# design.net
KiCad netlist of a schematic drawn in Altium Designer
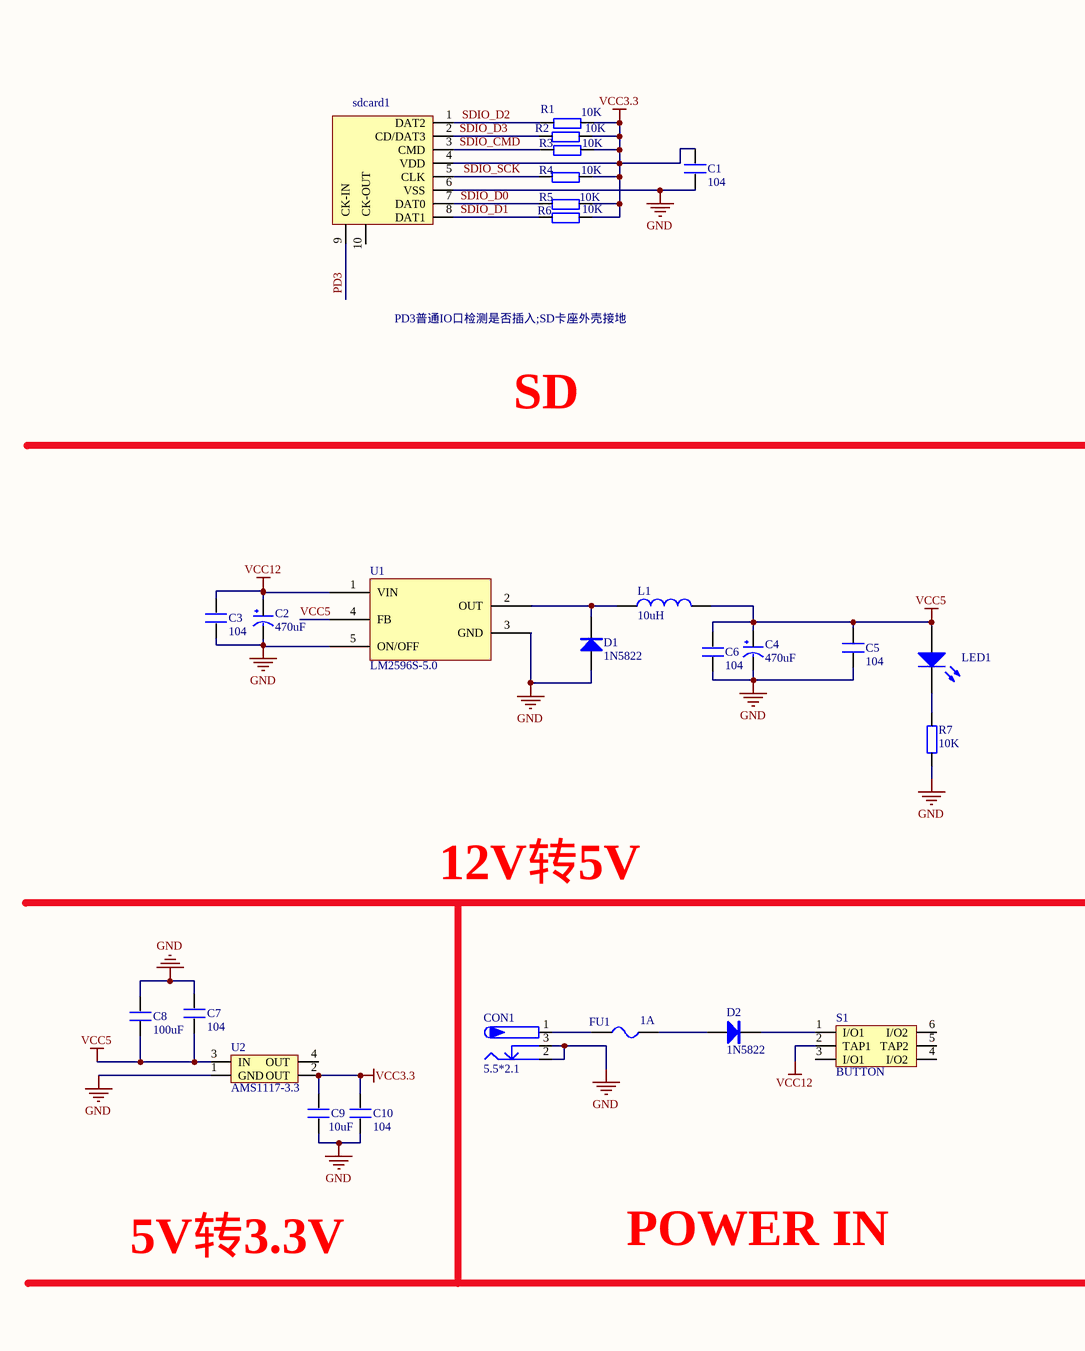
[diagram p0: 门禁原理图.SchDoc, top left]
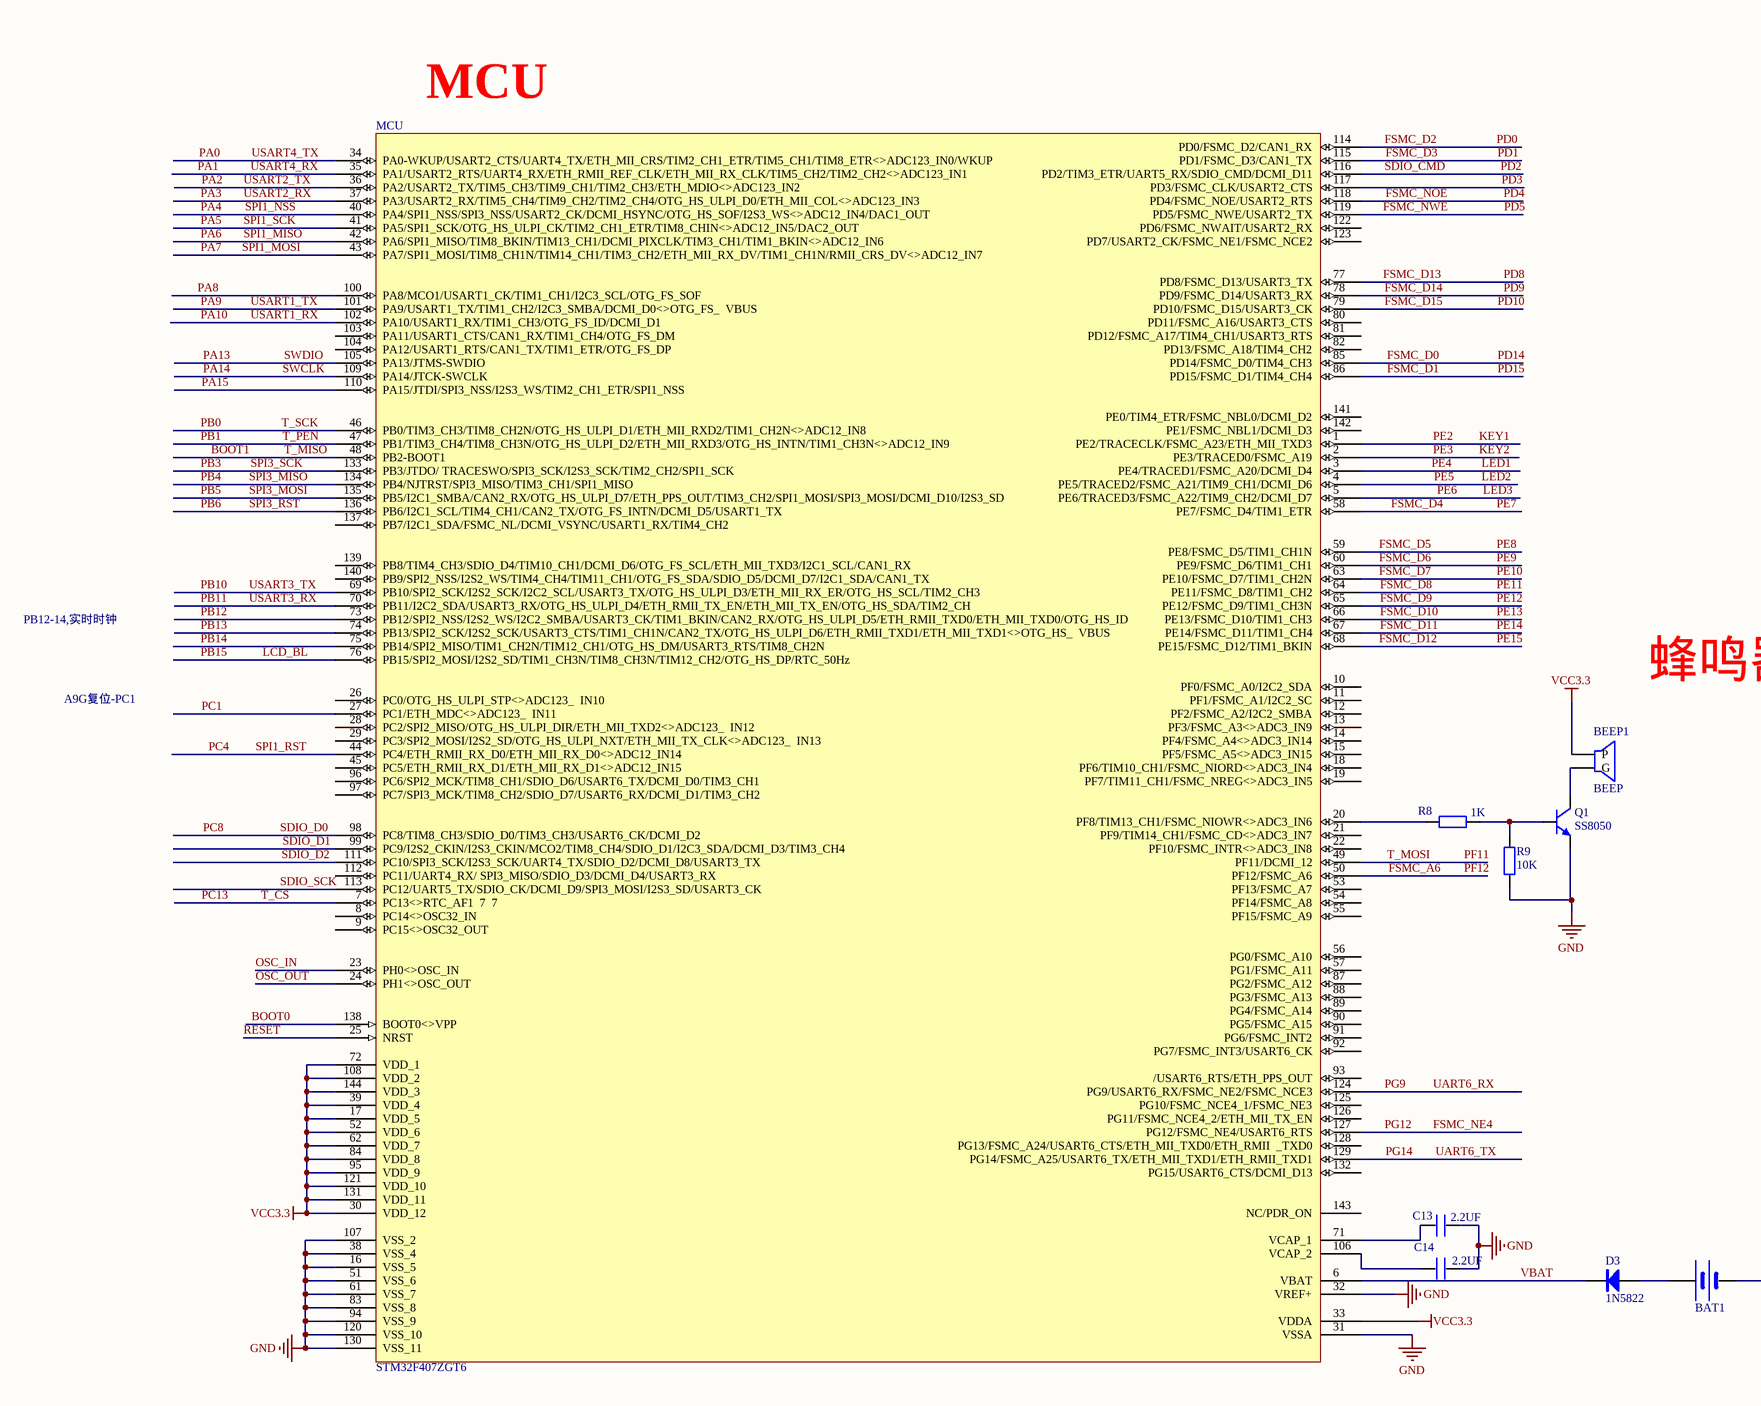
[diagram p1: 门禁原理图.SchDoc, top middle]
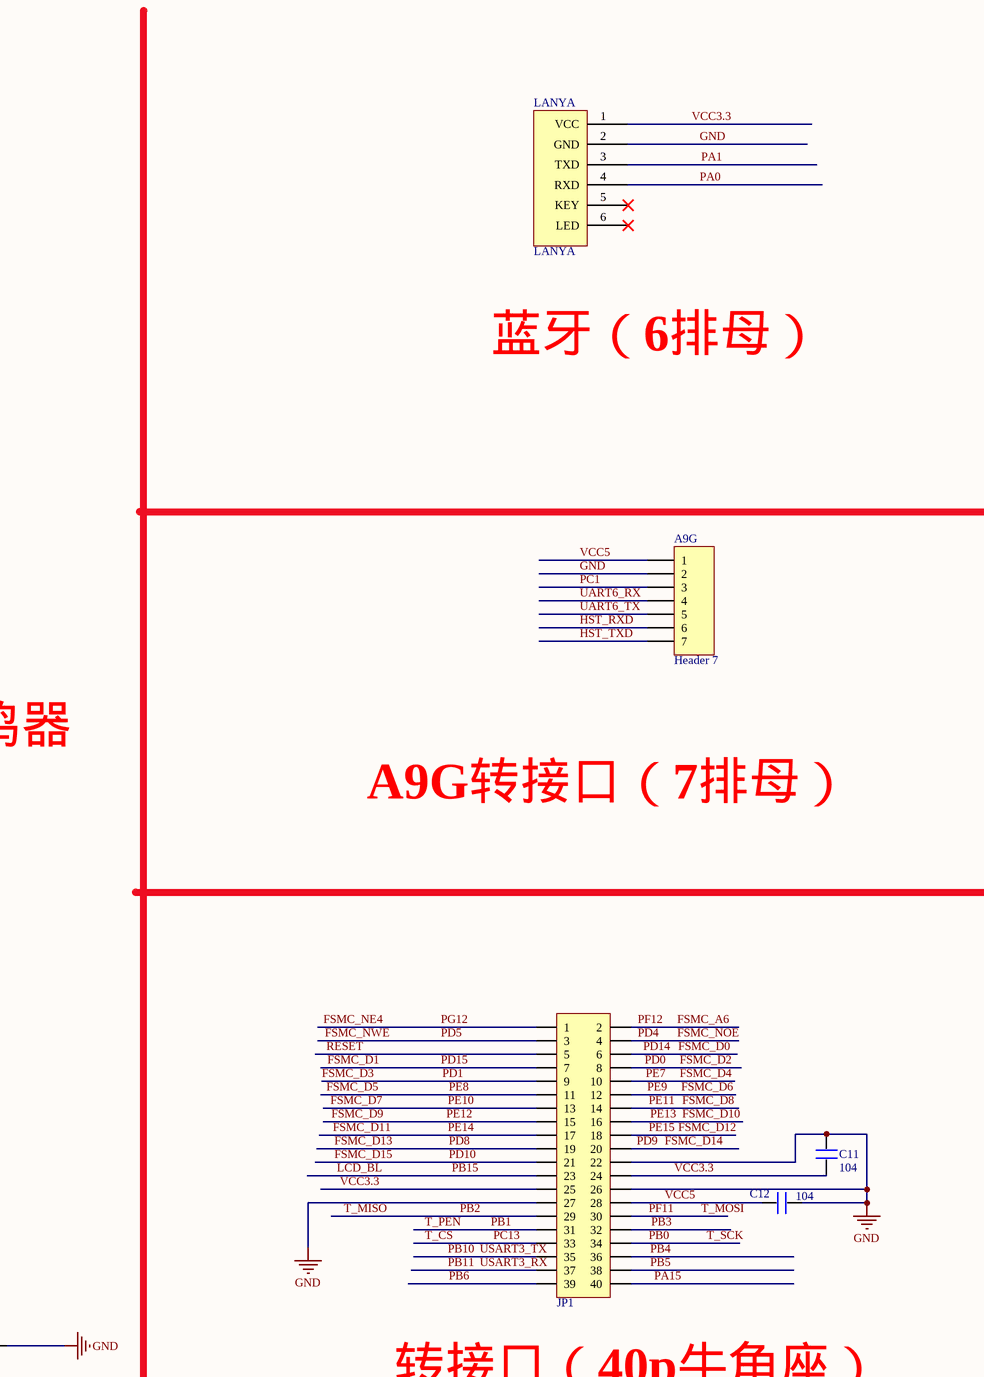
[diagram p2: 门禁原理图.SchDoc, top right]
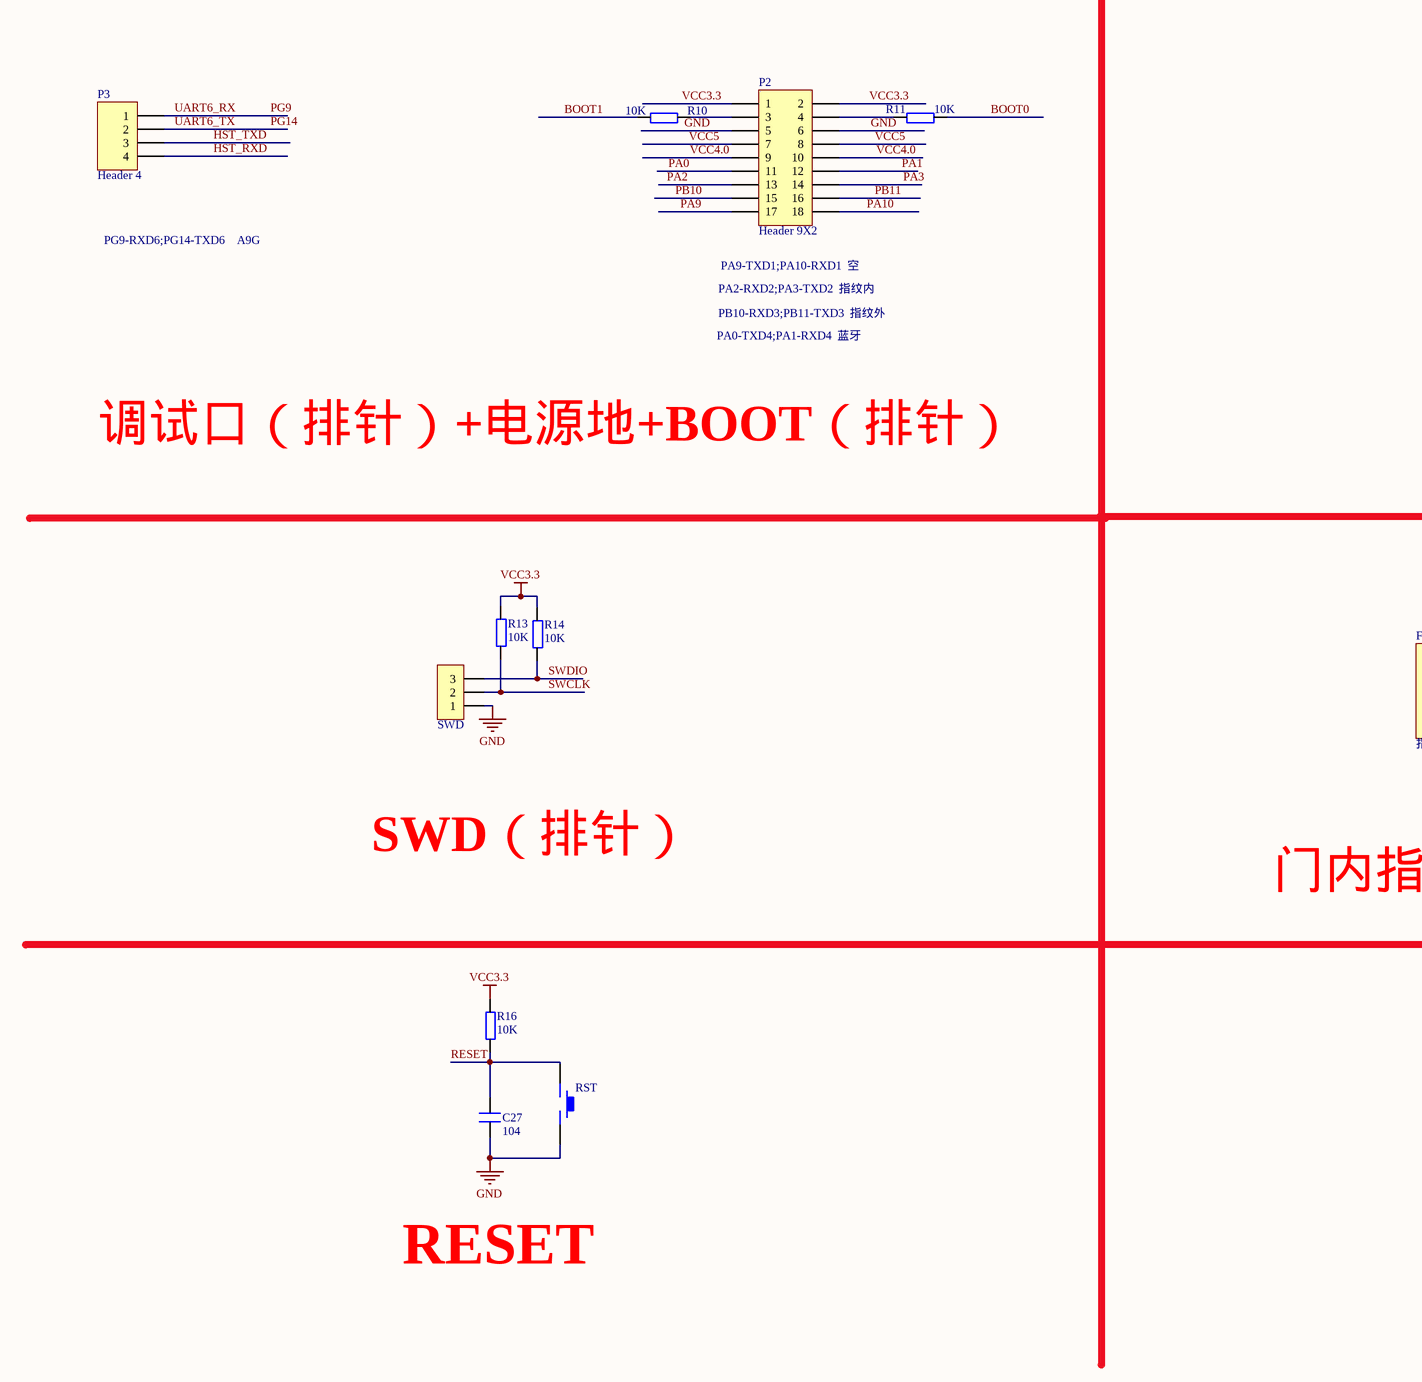
[diagram p3: 门禁原理图.SchDoc, bottom left]
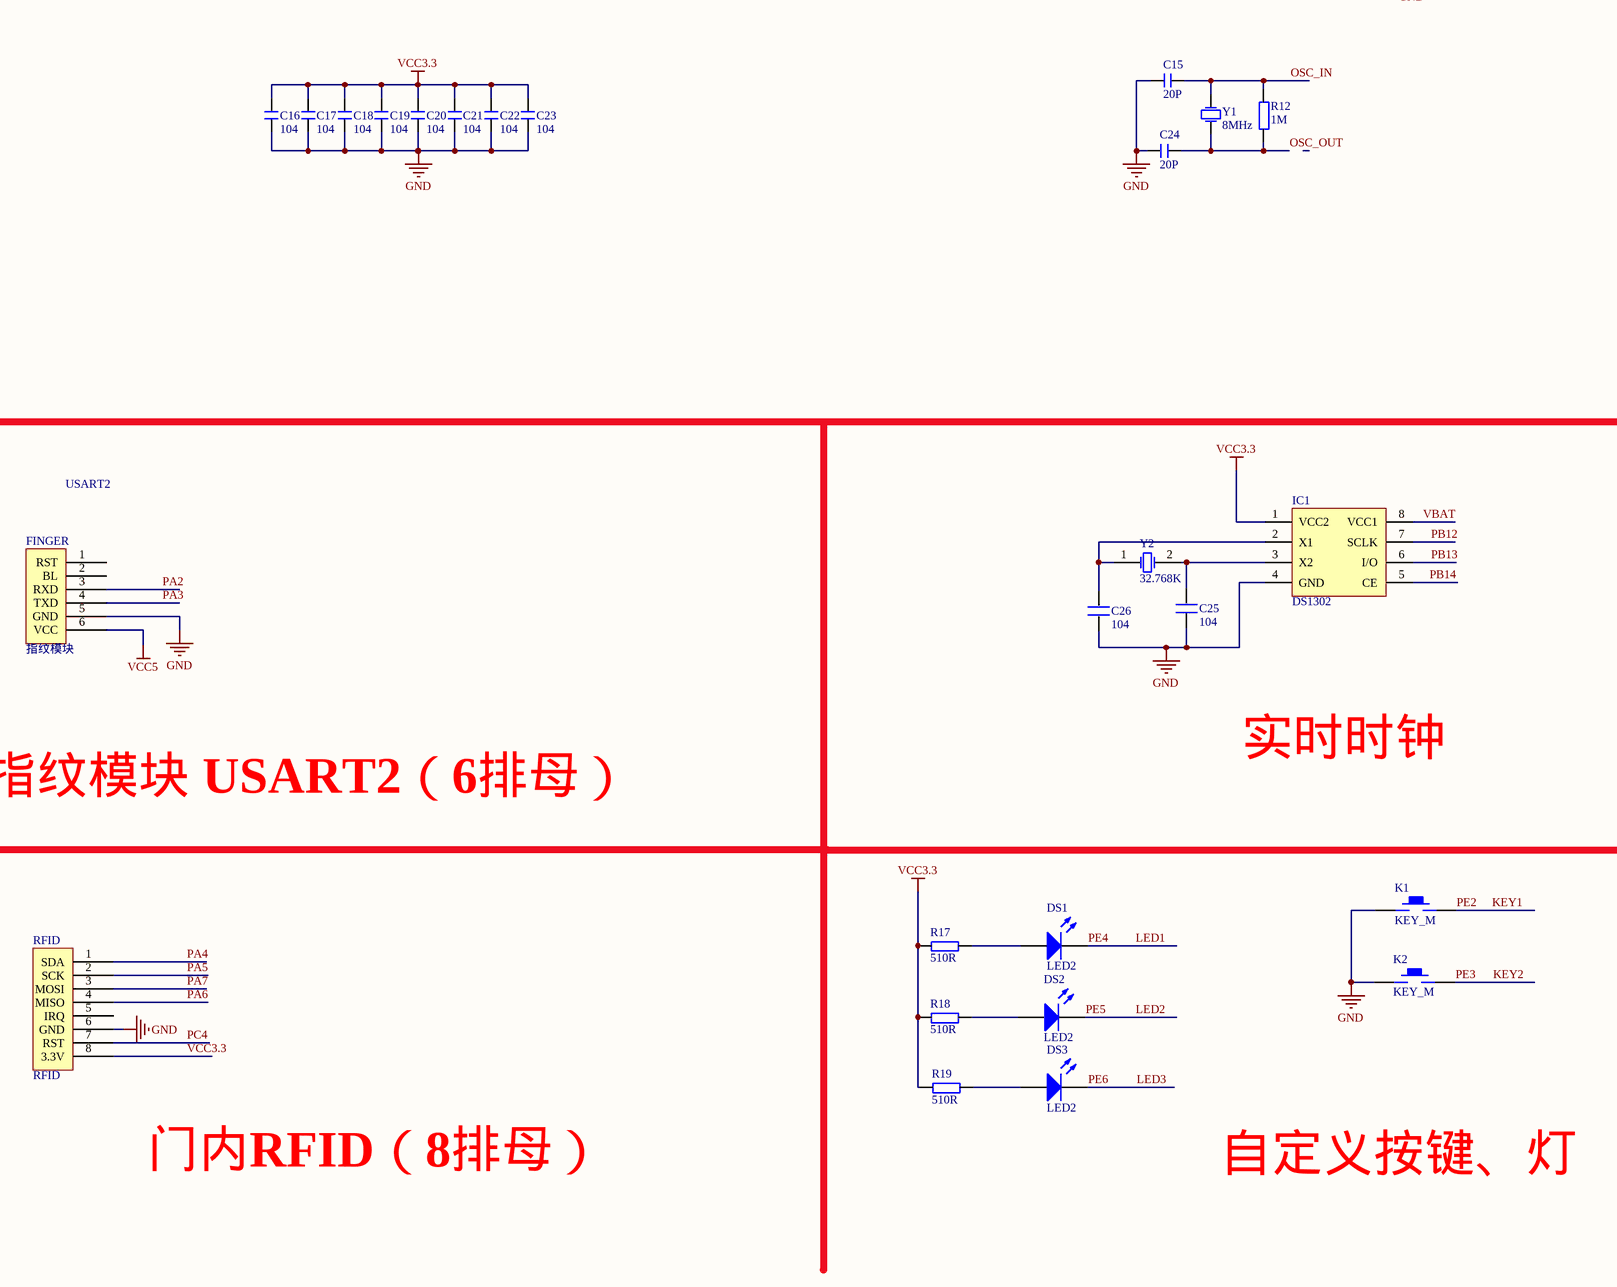
[diagram p4: 门禁原理图.SchDoc, bottom middle]
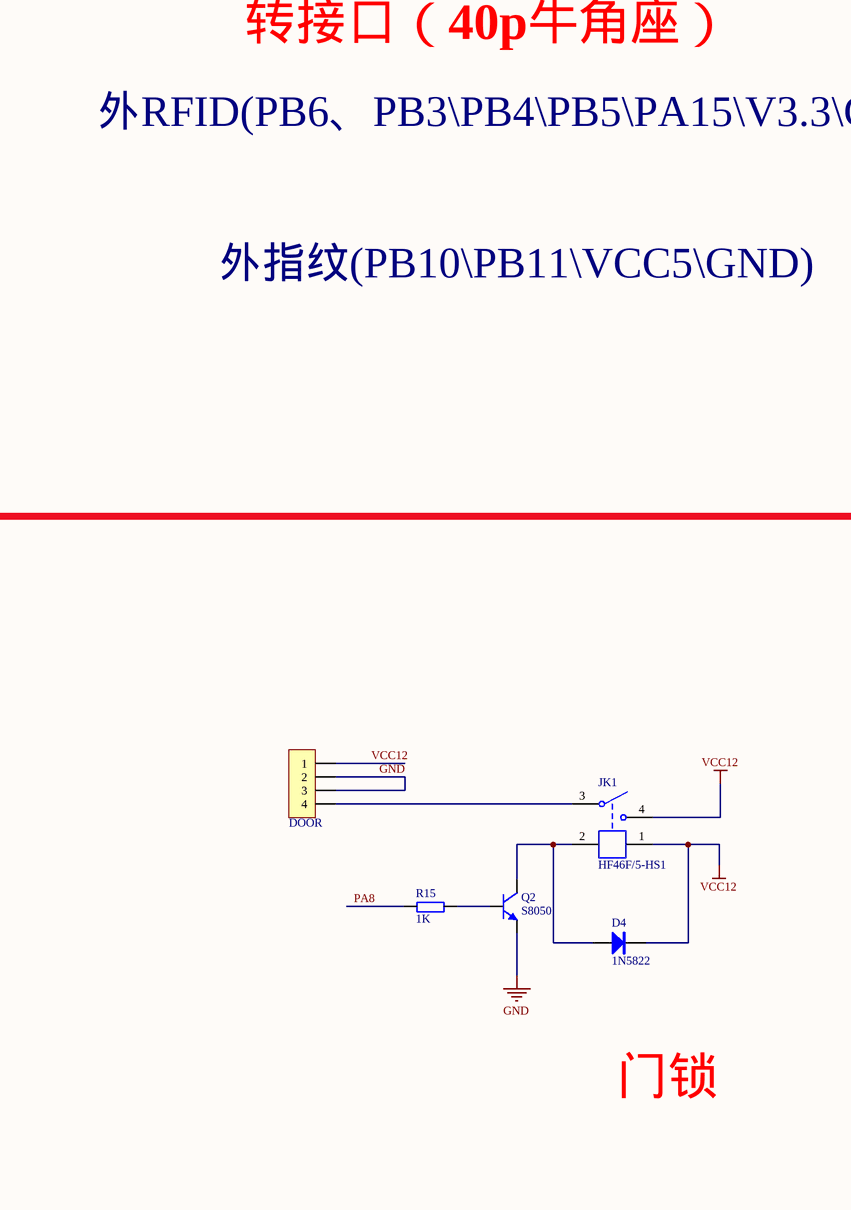
[diagram p5: 门禁原理图.SchDoc, bottom right]

(export (version "E")
  (design (tool "Eeschema 10.0.6"))
  (components
    (comp (ref "A9G")
      (value "Header 7")
      (footprint "A9G")
      (description "Header, 7-Pin")
      (fields (field (name "PUBLISHER") "Altium Limited"))
      (libsource (lib "Miscellaneous Connectors") (part "Header 7"))
    )
    (comp (ref "BAT1") (value "BATT") (footprint "BATMAX") (libsource (lib "门禁系统") (part "BAT")))
    (comp (ref "BEEP1") (value "BEEP") (footprint "BUZZ") (libsource (lib "门禁系统") (part "BEEP")))
    (comp (ref "C1") (value "104") (footprint "0805") (libsource (lib "Explorer STM32F407封装库") (part "C")))
    (comp (ref "C2") (value "470uF") (footprint "CM F(10*10.2)") (libsource (lib "门禁系统") (part "CAP")))
    (comp (ref "C3") (value "104") (footprint "0805") (libsource (lib "门禁系统") (part "C")))
    (comp (ref "C4") (value "470uF") (footprint "CM F(10*10.2)") (libsource (lib "门禁系统") (part "CAP")))
    (comp (ref "C5") (value "104") (footprint "0805") (libsource (lib "门禁系统") (part "C")))
    (comp (ref "C6") (value "104") (footprint "0805") (libsource (lib "门禁系统") (part "C")))
    (comp (ref "C7") (value "104") (footprint "0603P") (libsource (lib "Explorer STM32F407封装库") (part "C")))
    (comp (ref "C8")
      (value "100uF")
      (footprint "CM D(6.3*7.7)")
      (libsource (lib "Explorer STM32F407封装库") (part "C"))
    )
    (comp (ref "C9") (value "10uF") (footprint "0603P") (libsource (lib "Explorer STM32F407封装库") (part "C")))
    (comp (ref "C10") (value "104") (footprint "0603P") (libsource (lib "Explorer STM32F407封装库") (part "C")))
    (comp (ref "C11") (value "104") (footprint "0805") (libsource (lib "Explorer STM32F407封装库") (part "C")))
    (comp (ref "C12") (value "104") (footprint "0805") (libsource (lib "Explorer STM32F407封装库") (part "C")))
    (comp (ref "C13")
      (value "2.2UF")
      (footprint "0805")
      (libsource (lib "Explorer STM32F407封装库_SCH") (part "C_1"))
    )
    (comp (ref "C14")
      (value "2.2UF")
      (footprint "0805")
      (libsource (lib "Explorer STM32F407封装库_SCH") (part "C_1"))
    )
    (comp (ref "C15")
      (value "20P")
      (footprint "0805")
      (description "无极性贴片电容")
      (fields (field (name "版权归属") "源创客"))
      (libsource (lib "3.1   - 电阻-电容-电感") (part "C"))
    )
    (comp (ref "C16")
      (value "104")
      (footprint "0805")
      (description "无极性贴片电容")
      (fields (field (name "版权归属") "源创客"))
      (libsource (lib "3.1   - 电阻-电容-电感") (part "C"))
    )
    (comp (ref "C17")
      (value "104")
      (footprint "0805")
      (description "无极性贴片电容")
      (fields (field (name "版权归属") "源创客"))
      (libsource (lib "3.1   - 电阻-电容-电感") (part "C"))
    )
    (comp (ref "C18")
      (value "104")
      (footprint "0805")
      (description "无极性贴片电容")
      (fields (field (name "版权归属") "源创客"))
      (libsource (lib "3.1   - 电阻-电容-电感") (part "C"))
    )
    (comp (ref "C19")
      (value "104")
      (footprint "0805")
      (description "无极性贴片电容")
      (fields (field (name "版权归属") "源创客"))
      (libsource (lib "3.1   - 电阻-电容-电感") (part "C"))
    )
    (comp (ref "C20")
      (value "104")
      (footprint "0805")
      (description "无极性贴片电容")
      (fields (field (name "版权归属") "源创客"))
      (libsource (lib "3.1   - 电阻-电容-电感") (part "C"))
    )
    (comp (ref "C21")
      (value "104")
      (footprint "0805")
      (description "无极性贴片电容")
      (fields (field (name "版权归属") "源创客"))
      (libsource (lib "3.1   - 电阻-电容-电感") (part "C"))
    )
    (comp (ref "C22")
      (value "104")
      (footprint "0805")
      (description "无极性贴片电容")
      (fields (field (name "版权归属") "源创客"))
      (libsource (lib "3.1   - 电阻-电容-电感") (part "C"))
    )
    (comp (ref "C23")
      (value "104")
      (footprint "0805")
      (description "无极性贴片电容")
      (fields (field (name "版权归属") "源创客"))
      (libsource (lib "3.1   - 电阻-电容-电感") (part "C"))
    )
    (comp (ref "C24")
      (value "20P")
      (footprint "0805")
      (description "无极性贴片电容")
      (fields (field (name "版权归属") "源创客"))
      (libsource (lib "3.1   - 电阻-电容-电感") (part "C"))
    )
    (comp (ref "C25") (value "104") (footprint "0805") (libsource (lib "门禁系统") (part "C")))
    (comp (ref "C26") (value "104") (footprint "0805") (libsource (lib "门禁系统") (part "C")))
    (comp (ref "C27")
      (value "104")
      (footprint "0603P")
      (libsource (lib "Explorer STM32F407封装库_SCH") (part "C"))
    )
    (comp (ref "CON1")
      (value "5.5*2.1")
      (footprint "DC-005")
      (description "低压电源接口")
      (fields (field (name "版权归属") "源创客"))
      (libsource (lib "4.1   - 接口类") (part "P-DC"))
    )
    (comp (ref "D1")
      (value "1N5822")
      (footprint "DIODE_3*5.3")
      (description "高速开关二极管")
      (fields (field (name "版权归属") "源创客"))
      (libsource (lib "8.1   - 二极管-整流桥") (part "1N4148"))
    )
    (comp (ref "D2")
      (value "1N5822")
      (footprint "DIODE_3*5.3")
      (description "高速开关二极管")
      (fields (field (name "版权归属") "源创客"))
      (libsource (lib "8.1   - 二极管-整流桥") (part "1N4148"))
    )
    (comp (ref "D3")
      (value "1N5822")
      (footprint "DIODE_3*5.3")
      (description "高速开关二极管")
      (fields (field (name "版权归属") "源创客"))
      (libsource (lib "8.1   - 二极管-整流桥") (part "1N4148"))
    )
    (comp (ref "D4")
      (value "1N5822")
      (footprint "DIODE_3*5.3")
      (description "高速开关二极管")
      (fields (field (name "版权归属") "源创客"))
      (libsource (lib "8.1   - 二极管-整流桥") (part "1N4148"))
    )
    (comp (ref "DOOR")
      (value "HDR-1X4")
      (footprint "XH2.54-WI-4P")
      (description "4P接插件")
      (fields (field (name "版权归属") "源创客"))
      (libsource (lib "4.5   - 接插件-脚距2.54") (part "Header 4"))
    )
    (comp (ref "DS1")
      (value "LED2")
      (footprint "SMDLED")
      (description "Typical RED, GREEN, YELLOW, AMBER GaAs LED")
      (fields (field (name "PUBLISHER") "*"))
      (libsource (lib "Explorer STM32F407封装库_SCH") (part "LED2"))
    )
    (comp (ref "DS2")
      (value "LED2")
      (footprint "SMDLED")
      (description "Typical RED, GREEN, YELLOW, AMBER GaAs LED")
      (fields (field (name "PUBLISHER") "*"))
      (libsource (lib "Explorer STM32F407封装库_SCH") (part "LED2"))
    )
    (comp (ref "DS3")
      (value "LED2")
      (footprint "SMDLED")
      (description "Typical RED, GREEN, YELLOW, AMBER GaAs LED")
      (fields (field (name "PUBLISHER") "*"))
      (libsource (lib "Explorer STM32F407封装库_SCH") (part "LED2"))
    )
    (comp (ref "FINGER") (value "指纹模块") (footprint "指纹") (libsource (lib "Schlib1") (part "指纹模块")))
    (comp (ref "FU1")
      (value "1A")
      (footprint "FU 1812")
      (description "贴片保险丝")
      (fields (field (name "版权归属") "源创客"))
      (libsource (lib "10.1 - 保险丝-晶振") (part "FU"))
    )
    (comp (ref "IC1")
      (value "DS1302")
      (footprint "SOP8_N")
      (description "实时时钟芯片")
      (fields (field (name "版权归属") "源创客"))
      (libsource (lib "1.1   - IC芯片") (part "DS1302"))
    )
    (comp (ref "JK1")
      (value "HF46F/5-HS1")
      (footprint "HF46-xx-HS1")
      (description "5V一组常开")
      (fields (field (name "版权归属") "源创客"))
      (libsource (lib "7.1   - 继电器") (part "HF46F/5-HS1"))
    )
    (comp (ref "JP1")
      (value "Header 2X11")
      (footprint "IDC2.54-LI-2x20P")
      (description "20*2P接插件")
      (fields (field (name "版权归属") "源创客"))
      (libsource (lib "4.5   - 接插件-脚距2.54") (part "Header 20X2"))
    )
    (comp (ref "K1")
      (value "KEY_M")
      (footprint "KEY_M")
      (libsource (lib "Explorer STM32F407封装库_SCH") (part "KEY_M"))
    )
    (comp (ref "K2")
      (value "KEY_M")
      (footprint "KEY_M")
      (libsource (lib "Explorer STM32F407封装库_SCH") (part "KEY_M"))
    )
    (comp (ref "L1")
      (value "10uH")
      (footprint "0805")
      (description "小功率贴片电感")
      (fields (field (name "版权归属") "源创客"))
      (libsource (lib "3.1   - 电阻-电容-电感") (part "L"))
    )
    (comp (ref "LANYA") (value "LANYA") (footprint "蓝牙") (libsource (lib "Schlib1") (part "蓝牙模块")))
    (comp (ref "LED1")
      (value "LED1")
      (footprint "SMDLED")
      (description "Typical RED, GREEN, YELLOW, AMBER GaAs LED")
      (fields (field (name "PUBLISHER") "Altium Limited"))
      (libsource (lib "门禁系统") (part "LED2"))
    )
    (comp (ref "MCU")
      (value "STM32F407ZGT6")
      (footprint "LQFP144")
      (libsource (lib "STM32F407 ") (part "STM32F407ZGT6"))
    )
    (comp (ref "P2")
      (value "Header 9X2")
      (footprint "HDR2X9")
      (description "Header, 9-Pin, Dual row")
      (fields (field (name "PUBLISHER") "Altium Limited"))
      (libsource (lib "Miscellaneous Connectors") (part "Header 9X2"))
    )
    (comp (ref "P3")
      (value "Header 4")
      (footprint "HDR1X4")
      (description "Header, 4-Pin")
      (fields (field (name "PUBLISHER") "Altium Limited"))
      (libsource (lib "Miscellaneous Connectors") (part "Header 4"))
    )
    (comp (ref "Q1")
      (value "SS8050")
      (footprint "SOT23-3N")
      (description "高频放大-NPN型")
      (fields (field (name "版权归属") "源创客"))
      (libsource (lib "6.2   - 三极管") (part "8050-SMD"))
    )
    (comp (ref "Q2")
      (value "S8050")
      (footprint "SOT23-3N")
      (description "高频放大-NPN型")
      (fields (field (name "版权归属") "源创客"))
      (libsource (lib "6.2   - 三极管") (part "8050-SMD"))
    )
    (comp (ref "R1") (value "10K") (footprint "0805") (libsource (lib "Explorer STM32F407封装库") (part "R")))
    (comp (ref "R2") (value "10K") (footprint "0805") (libsource (lib "Explorer STM32F407封装库") (part "R")))
    (comp (ref "R3") (value "10K") (footprint "0805") (libsource (lib "Explorer STM32F407封装库") (part "R")))
    (comp (ref "R4") (value "10K") (footprint "0805") (libsource (lib "Explorer STM32F407封装库") (part "R")))
    (comp (ref "R5") (value "10K") (footprint "0805") (libsource (lib "Explorer STM32F407封装库") (part "R")))
    (comp (ref "R6") (value "10K") (footprint "0805") (libsource (lib "Explorer STM32F407封装库") (part "R")))
    (comp (ref "R7") (value "10K") (footprint "0805") (libsource (lib "门禁系统") (part "R")))
    (comp (ref "R8")
      (value "1K")
      (footprint "0805")
      (description "贴片电阻")
      (fields (field (name "版权归属") "源创客"))
      (libsource (lib "3.1   - 电阻-电容-电感") (part "R"))
    )
    (comp (ref "R9")
      (value "10K")
      (footprint "0805")
      (description "贴片电阻")
      (fields (field (name "版权归属") "源创客"))
      (libsource (lib "3.1   - 电阻-电容-电感") (part "R"))
    )
    (comp (ref "R10") (value "10K") (footprint "0805") (libsource (lib "Explorer STM32F407封装库") (part "R")))
    (comp (ref "R11")
      (value "10K")
      (footprint "0805")
      (libsource (lib "Explorer STM32F407封装库_SCH") (part "R"))
    )
    (comp (ref "R12") (value "1M") (footprint "0805") (libsource (lib "门禁系统") (part "R")))
    (comp (ref "R13") (value "10K") (footprint "0805") (libsource (lib "WarShip V3 STM32103封装库") (part "R")))
    (comp (ref "R14") (value "10K") (footprint "0805") (libsource (lib "WarShip V3 STM32103封装库") (part "R")))
    (comp (ref "R15")
      (value "1K")
      (footprint "0805")
      (libsource (lib "Explorer STM32F407封装库_SCH") (part "R"))
    )
    (comp (ref "R16")
      (value "10K")
      (footprint "0805")
      (libsource (lib "Explorer STM32F407封装库_SCH") (part "R"))
    )
    (comp (ref "R17")
      (value "510R")
      (footprint "0805")
      (libsource (lib "Explorer STM32F407封装库_SCH") (part "R"))
    )
    (comp (ref "R18")
      (value "510R")
      (footprint "0805")
      (libsource (lib "Explorer STM32F407封装库_SCH") (part "R"))
    )
    (comp (ref "R19")
      (value "510R")
      (footprint "0805")
      (libsource (lib "Explorer STM32F407封装库_SCH") (part "R"))
    )
    (comp (ref "RFID") (value "RFID") (footprint "RFID") (libsource (lib "Schlib1") (part "RC522")))
    (comp (ref "RST") (value "~") (footprint "KEY_M") (libsource (lib "") (part "KEY_M_1")))
    (comp (ref "S1") (value "BUTTON") (footprint "BTN8.5*8.5") (libsource (lib "门禁系统") (part "BUTTON")))
    (comp (ref "sdcard1")
      (value "sdIO-sdcard")
      (footprint "sdcard_2")
      (libsource (lib "门禁系统") (part "sdIO-sdcard"))
    )
    (comp (ref "SWD")
      (value "HDR-1X3")
      (footprint "HDR2.54-LI-3P")
      (description "3P接插件")
      (fields (field (name "版权归属") "源创客"))
      (libsource (lib "4.10 - 接插件-脚距5.08") (part "Header 3"))
    )
    (comp (ref "U1")
      (value "LM2596S-5.0")
      (footprint "TO263-5A")
      (description "LM2576S-5.0")
      (libsource (lib "Schlib1") (part "Component_1"))
    )
    (comp (ref "U2") (value "AMS1117-3.3") (footprint "AMS1117") (libsource (lib "门禁系统") (part "AMS1117")))
    (comp (ref "Y1")
      (value "8MHz")
      (footprint "XTAL_T")
      (description "Crystal Oscillator")
      (fields (field (name "PUBLISHER") "Altium Limited"))
      (libsource (lib "门禁系统") (part "XTAL_2"))
    )
    (comp (ref "Y2")
      (value "32.768K")
      (footprint "XTAL32")
      (description "Crystal Oscillator")
      (fields (field (name "PUBLISHER") "Altium Limited"))
      (libsource (lib "门禁系统") (part "XTAL_1"))
    )
  )
  (nets
    (net (code "2") (name "/BOOT0") (class "Default")
      (node (ref "MCU") (pin "138") (pinfunction "BOOT0<>VPP_138") (pintype "input"))
      (node (ref "R11") (pin "2") (pintype "passive"))
    )
    (net (code "3") (name "/BOOT1") (class "Default")
      (node (ref "JP1") (pin "29") (pinfunction "29_29") (pintype "passive"))
      (node (ref "MCU") (pin "48") (pinfunction "PB2-BOOT1_48") (pintype "bidirectional"))
      (node (ref "R10") (pin "1") (pintype "passive"))
    )
    (net (code "4") (name "/FSMC_A6") (class "Default")
      (node (ref "JP1") (pin "2") (pinfunction "2_2") (pintype "passive"))
      (node (ref "MCU") (pin "50") (pinfunction "PF12/FSMC_A6_50") (pintype "bidirectional"))
    )
    (net (code "5") (name "/FSMC_D0") (class "Default")
      (node (ref "JP1") (pin "6") (pinfunction "6_6") (pintype "passive"))
      (node (ref "MCU") (pin "85") (pinfunction "PD14/FSMC_D0/TIM4_CH3_85") (pintype "bidirectional"))
    )
    (net (code "6") (name "/FSMC_D1") (class "Default")
      (node (ref "JP1") (pin "7") (pinfunction "7_7") (pintype "passive"))
      (node (ref "MCU") (pin "86") (pinfunction "PD15/FSMC_D1/TIM4_CH4_86") (pintype "bidirectional"))
    )
    (net (code "7") (name "/FSMC_D2") (class "Default")
      (node (ref "JP1") (pin "8") (pinfunction "8_8") (pintype "passive"))
      (node (ref "MCU") (pin "114") (pinfunction "PD0/FSMC_D2/CAN1_RX_114") (pintype "bidirectional"))
    )
    (net (code "8") (name "/FSMC_D3") (class "Default")
      (node (ref "JP1") (pin "9") (pinfunction "9_9") (pintype "passive"))
      (node (ref "MCU") (pin "115") (pinfunction "PD1/FSMC_D3/CAN1_TX_115") (pintype "bidirectional"))
    )
    (net (code "9") (name "/FSMC_D4") (class "Default")
      (node (ref "JP1") (pin "10") (pinfunction "10_10") (pintype "passive"))
      (node (ref "MCU") (pin "58") (pinfunction "PE7/FSMC_D4/TIM1_ETR_58") (pintype "bidirectional"))
    )
    (net (code "10") (name "/FSMC_D5") (class "Default")
      (node (ref "JP1") (pin "11") (pinfunction "11_11") (pintype "passive"))
      (node (ref "MCU") (pin "59") (pinfunction "PE8/FSMC_D5/TIM1_CH1N_59") (pintype "bidirectional"))
    )
    (net (code "11") (name "/FSMC_D6") (class "Default")
      (node (ref "JP1") (pin "12") (pinfunction "12_12") (pintype "passive"))
      (node (ref "MCU") (pin "60") (pinfunction "PE9/FSMC_D6/TIM1_CH1_60") (pintype "bidirectional"))
    )
    (net (code "12") (name "/FSMC_D7") (class "Default")
      (node (ref "JP1") (pin "13") (pinfunction "13_13") (pintype "passive"))
      (node (ref "MCU") (pin "63") (pinfunction "PE10/FSMC_D7/TIM1_CH2N_63") (pintype "bidirectional"))
    )
    (net (code "13") (name "/FSMC_D8") (class "Default")
      (node (ref "JP1") (pin "14") (pinfunction "14_14") (pintype "passive"))
      (node (ref "MCU") (pin "64") (pinfunction "PE11/FSMC_D8/TIM1_CH2_64") (pintype "bidirectional"))
    )
    (net (code "14") (name "/FSMC_D9") (class "Default")
      (node (ref "JP1") (pin "15") (pinfunction "15_15") (pintype "passive"))
      (node (ref "MCU") (pin "65") (pinfunction "PE12/FSMC_D9/TIM1_CH3N_65") (pintype "bidirectional"))
    )
    (net (code "15") (name "/FSMC_D10") (class "Default")
      (node (ref "JP1") (pin "16") (pinfunction "16_16") (pintype "passive"))
      (node (ref "MCU") (pin "66") (pinfunction "PE13/FSMC_D10/TIM1_CH3_66") (pintype "bidirectional"))
    )
    (net (code "16") (name "/FSMC_D11") (class "Default")
      (node (ref "JP1") (pin "17") (pinfunction "17_17") (pintype "passive"))
      (node (ref "MCU") (pin "67") (pinfunction "PE14/FSMC_D11/TIM1_CH4_67") (pintype "bidirectional"))
    )
    (net (code "17") (name "/FSMC_D12") (class "Default")
      (node (ref "JP1") (pin "18") (pinfunction "18_18") (pintype "passive"))
      (node (ref "MCU") (pin "68") (pinfunction "PE15/FSMC_D12/TIM1_BKIN_68") (pintype "bidirectional"))
    )
    (net (code "18") (name "/FSMC_D13") (class "Default")
      (node (ref "JP1") (pin "19") (pinfunction "19_19") (pintype "passive"))
      (node (ref "MCU") (pin "77") (pinfunction "PD8/FSMC_D13/USART3_TX_77") (pintype "bidirectional"))
    )
    (net (code "19") (name "/FSMC_D14") (class "Default")
      (node (ref "JP1") (pin "20") (pinfunction "20_20") (pintype "passive"))
      (node (ref "MCU") (pin "78") (pinfunction "PD9/FSMC_D14/USART3_RX_78") (pintype "bidirectional"))
    )
    (net (code "20") (name "/FSMC_D15") (class "Default")
      (node (ref "JP1") (pin "21") (pinfunction "21_21") (pintype "passive"))
      (node (ref "MCU") (pin "79") (pinfunction "PD10/FSMC_D15/USART3_CK_79") (pintype "bidirectional"))
    )
    (net (code "21") (name "/FSMC_NE4") (class "Default")
      (node (ref "JP1") (pin "1") (pinfunction "1_1") (pintype "passive"))
      (node (ref "MCU") (pin "127") (pinfunction "PG12/FSMC_NE4/USART6_RTS_127") (pintype "bidirectional"))
    )
    (net (code "22") (name "/FSMC_NOE") (class "Default")
      (node (ref "JP1") (pin "4") (pinfunction "4_4") (pintype "passive"))
      (node (ref "MCU") (pin "118") (pinfunction "PD4/FSMC_NOE/USART2_RTS_118") (pintype "bidirectional"))
    )
    (net (code "23") (name "/FSMC_NWE") (class "Default")
      (node (ref "JP1") (pin "3") (pinfunction "3_3") (pintype "passive"))
      (node (ref "MCU") (pin "119") (pinfunction "PD5/FSMC_NWE/USART2_TX_119") (pintype "bidirectional"))
    )
    (net (code "24") (name "/HST_RXD") (class "Default")
      (node (ref "A9G") (pin "6") (pinfunction "6_6") (pintype "passive"))
      (node (ref "P3") (pin "4") (pinfunction "4_4") (pintype "passive"))
    )
    (net (code "25") (name "/HST_TXD") (class "Default")
      (node (ref "A9G") (pin "7") (pinfunction "7_7") (pintype "passive"))
      (node (ref "P3") (pin "3") (pinfunction "3_3") (pintype "passive"))
    )
    (net (code "26") (name "/KEY1") (class "Default")
      (node (ref "K1") (pin "2") (pinfunction "2_2") (pintype "passive"))
      (node (ref "MCU") (pin "1") (pinfunction "PE2/TRACECLK/FSMC_A23/ETH_MII_TXD3_1") (pintype "bidirectional"))
    )
    (net (code "27") (name "/KEY2") (class "Default")
      (node (ref "K2") (pin "2") (pinfunction "2_2") (pintype "passive"))
      (node (ref "MCU") (pin "2") (pinfunction "PE3/TRACED0/FSMC_A19_2") (pintype "bidirectional"))
    )
    (net (code "28") (name "/LCD_BL") (class "Default")
      (node (ref "JP1") (pin "23") (pinfunction "23_23") (pintype "passive"))
      (node (ref "MCU") (pin "76") (pinfunction "PB15/SPI2_MOSI/I2S2_SD/TIM1_CH3N/TIM8_CH3N/TIM12_CH2/OTG_HS_DP/RTC_50Hz_76") (pintype "bidirectional"))
    )
    (net (code "29") (name "/LED1") (class "Default")
      (node (ref "DS1") (pin "2") (pinfunction "K_2") (pintype "passive"))
      (node (ref "MCU") (pin "3") (pinfunction "PE4/TRACED1/FSMC_A20/DCMI_D4_3") (pintype "bidirectional"))
    )
    (net (code "30") (name "/LED2") (class "Default")
      (node (ref "DS2") (pin "2") (pinfunction "K_2") (pintype "passive"))
      (node (ref "MCU") (pin "4") (pinfunction "PE5/TRACED2/FSMC_A21/TIM9_CH1/DCMI_D6_4") (pintype "bidirectional"))
    )
    (net (code "31") (name "/LED3") (class "Default")
      (node (ref "DS3") (pin "2") (pinfunction "K_2") (pintype "passive"))
      (node (ref "MCU") (pin "5") (pinfunction "PE6/TRACED3/FSMC_A22/TIM9_CH2/DCMI_D7_5") (pintype "bidirectional"))
    )
    (net (code "32") (name "/OSC_IN") (class "Default")
      (node (ref "C15") (pin "1") (pinfunction "1_1") (pintype "passive"))
      (node (ref "MCU") (pin "23") (pinfunction "PH0<>OSC_IN_23") (pintype "bidirectional"))
      (node (ref "R12") (pin "2") (pintype "passive"))
      (node (ref "Y1") (pin "2") (pinfunction "OSC2_2") (pintype "passive"))
    )
    (net (code "33") (name "/OSC_OUT") (class "Default")
      (node (ref "C24") (pin "1") (pinfunction "1_1") (pintype "passive"))
      (node (ref "MCU") (pin "24") (pinfunction "PH1<>OSC_OUT_24") (pintype "bidirectional"))
      (node (ref "R12") (pin "1") (pintype "passive"))
      (node (ref "Y1") (pin "1") (pinfunction "OSC1_1") (pintype "passive"))
    )
    (net (code "34") (name "/PA0") (class "Default")
      (node (ref "LANYA") (pin "4") (pinfunction "RXD_4") (pintype "passive"))
      (node (ref "MCU") (pin "34") (pinfunction "PA0-WKUP/USART2_CTS/UART4_TX/ETH_MII_CRS/TIM2_CH1_ETR/TIM5_CH1/TIM8_ETR<>ADC123_IN0/WKUP_34") (pintype "bidirectional"))
      (node (ref "P2") (pin "11") (pinfunction "11_11") (pintype "passive"))
    )
    (net (code "35") (name "/PA1") (class "Default")
      (node (ref "LANYA") (pin "3") (pinfunction "TXD_3") (pintype "passive"))
      (node (ref "MCU") (pin "35") (pinfunction "PA1/USART2_RTS/UART4_RX/ETH_RMII_REF_CLK/ETH_MII_RX_CLK/TIM5_CH2/TIM2_CH2<>ADC123_IN1_35") (pintype "bidirectional"))
      (node (ref "P2") (pin "12") (pinfunction "12_12") (pintype "passive"))
    )
    (net (code "36") (name "/PA2") (class "Default")
      (node (ref "FINGER") (pin "3") (pinfunction "RXD_3") (pintype "passive"))
      (node (ref "MCU") (pin "36") (pinfunction "PA2/USART2_TX/TIM5_CH3/TIM9_CH1/TIM2_CH3/ETH_MDIO<>ADC123_IN2_36") (pintype "bidirectional"))
      (node (ref "P2") (pin "13") (pinfunction "13_13") (pintype "passive"))
    )
    (net (code "37") (name "/PA3") (class "Default")
      (node (ref "FINGER") (pin "4") (pinfunction "TXD_4") (pintype "passive"))
      (node (ref "MCU") (pin "37") (pinfunction "PA3/USART2_RX/TIM5_CH4/TIM9_CH2/TIM2_CH4/OTG_HS_ULPI_D0/ETH_MII_COL<>ADC123_IN3_37") (pintype "bidirectional"))
      (node (ref "P2") (pin "14") (pinfunction "14_14") (pintype "passive"))
    )
    (net (code "38") (name "/PA4") (class "Default")
      (node (ref "MCU") (pin "40") (pinfunction "PA4/SPI1_NSS/SPI3_NSS/USART2_CK/DCMI_HSYNC/OTG_HS_SOF/I2S3_WS<>ADC12_IN4/DAC1_OUT_40") (pintype "bidirectional"))
      (node (ref "RFID") (pin "1") (pinfunction "SDA_1") (pintype "passive"))
    )
    (net (code "39") (name "/PA5") (class "Default")
      (node (ref "MCU") (pin "41") (pinfunction "PA5/SPI1_SCK/OTG_HS_ULPI_CK/TIM2_CH1_ETR/TIM8_CHIN<>ADC12_IN5/DAC2_OUT_41") (pintype "bidirectional"))
      (node (ref "RFID") (pin "2") (pinfunction "SCK_2") (pintype "passive"))
    )
    (net (code "40") (name "/PA6") (class "Default")
      (node (ref "MCU") (pin "42") (pinfunction "PA6/SPI1_MISO/TIM8_BKIN/TIM13_CH1/DCMI_PIXCLK/TIM3_CH1/TIM1_BKIN<>ADC12_IN6_42") (pintype "bidirectional"))
      (node (ref "RFID") (pin "4") (pinfunction "MISO_4") (pintype "passive"))
    )
    (net (code "41") (name "/PA7") (class "Default")
      (node (ref "MCU") (pin "43") (pinfunction "PA7/SPI1_MOSI/TIM8_CH1N/TIM14_CH1/TIM3_CH2/ETH_MII_RX_DV/TIM1_CH1N/RMII_CRS_DV<>ADC12_IN7_43") (pintype "bidirectional"))
      (node (ref "RFID") (pin "3") (pinfunction "MOSI_3") (pintype "passive"))
    )
    (net (code "42") (name "/PA8") (class "Default")
      (node (ref "MCU") (pin "100") (pinfunction "PA8/MCO1/USART1_CK/TIM1_CH1/I2C3_SCL/OTG_FS_SOF_100") (pintype "bidirectional"))
      (node (ref "R15") (pin "1") (pintype "passive"))
    )
    (net (code "43") (name "/PA9") (class "Default")
      (node (ref "MCU") (pin "101") (pinfunction "PA9/USART1_TX/TIM1_CH2/I2C3_SMBA/DCMI_D0<>OTG_FS___VBUS_101") (pintype "bidirectional"))
      (node (ref "P2") (pin "17") (pinfunction "17_17") (pintype "passive"))
    )
    (net (code "44") (name "/PA10") (class "Default")
      (node (ref "MCU") (pin "102") (pinfunction "PA10/USART1_RX/TIM1_CH3/OTG_FS_ID/DCMI_D1_102") (pintype "bidirectional"))
      (node (ref "P2") (pin "18") (pinfunction "18_18") (pintype "passive"))
    )
    (net (code "45") (name "/PA13") (class "Default")
      (node (ref "MCU") (pin "105") (pinfunction "PA13/JTMS-SWDIO_105") (pintype "bidirectional"))
      (node (ref "R14") (pin "1") (pintype "passive"))
      (node (ref "SWD") (pin "3") (pinfunction "3_3") (pintype "passive"))
    )
    (net (code "46") (name "/PA14") (class "Default")
      (node (ref "MCU") (pin "109") (pinfunction "PA14/JTCK-SWCLK_109") (pintype "bidirectional"))
      (node (ref "R13") (pin "1") (pintype "passive"))
      (node (ref "SWD") (pin "2") (pinfunction "2_2") (pintype "passive"))
    )
    (net (code "47") (name "/PA15") (class "Default")
      (node (ref "JP1") (pin "40") (pinfunction "40_40") (pintype "passive"))
      (node (ref "MCU") (pin "110") (pinfunction "PA15/JTDI/SPI3_NSS/I2S3_WS/TIM2_CH1_ETR/SPI1_NSS_110") (pintype "bidirectional"))
    )
    (net (code "48") (name "/PB0") (class "Default")
      (node (ref "JP1") (pin "34") (pinfunction "34_34") (pintype "passive"))
      (node (ref "MCU") (pin "46") (pinfunction "PB0/TIM3_CH3/TIM8_CH2N/OTG_HS_ULPI_D1/ETH_MII_RXD2/TIM1_CH2N<>ADC12_IN8_46") (pintype "bidirectional"))
    )
    (net (code "49") (name "/PB1") (class "Default")
      (node (ref "JP1") (pin "31") (pinfunction "31_31") (pintype "passive"))
      (node (ref "MCU") (pin "47") (pinfunction "PB1/TIM3_CH4/TIM8_CH3N/OTG_HS_ULPI_D2/ETH_MII_RXD3/OTG_HS_INTN/TIM1_CH3N<>ADC12_IN9_47") (pintype "bidirectional"))
    )
    (net (code "50") (name "/PB3") (class "Default")
      (node (ref "JP1") (pin "32") (pinfunction "32_32") (pintype "passive"))
      (node (ref "MCU") (pin "133") (pinfunction "PB3/JTDO/_TRACESWO/SPI3_SCK/I2S3_SCK/TIM2_CH2/SPI1_SCK_133") (pintype "bidirectional"))
    )
    (net (code "51") (name "/PB4") (class "Default")
      (node (ref "JP1") (pin "36") (pinfunction "36_36") (pintype "passive"))
      (node (ref "MCU") (pin "134") (pinfunction "PB4/NJTRST/SPI3_MISO/TIM3_CH1/SPI1_MISO_134") (pintype "bidirectional"))
    )
    (net (code "52") (name "/PB5") (class "Default")
      (node (ref "JP1") (pin "38") (pinfunction "38_38") (pintype "passive"))
      (node (ref "MCU") (pin "135") (pinfunction "PB5/I2C1_SMBA/CAN2_RX/OTG_HS_ULPI_D7/ETH_PPS_OUT/TIM3_CH2/SPI1_MOSI/SPI3_MOSI/DCMI_D10/I2S3_SD_135") (pintype "bidirectional"))
    )
    (net (code "53") (name "/PB6") (class "Default")
      (node (ref "JP1") (pin "39") (pinfunction "39_39") (pintype "passive"))
      (node (ref "MCU") (pin "136") (pinfunction "PB6/I2C1_SCL/TIM4_CH1/CAN2_TX/OTG_FS_INTN/DCMI_D5/USART1_TX_136") (pintype "bidirectional"))
    )
    (net (code "54") (name "/PB10") (class "Default")
      (node (ref "JP1") (pin "35") (pinfunction "35_35") (pintype "passive"))
      (node (ref "MCU") (pin "69") (pinfunction "PB10/SPI2_SCK/I2S2_SCK/I2C2_SCL/USART3_TX/OTG_HS_ULPI_D3/ETH_MII_RX_ER/OTG_HS_SCL/TIM2_CH3_69") (pintype "bidirectional"))
      (node (ref "P2") (pin "15") (pinfunction "15_15") (pintype "passive"))
    )
    (net (code "55") (name "/PB11") (class "Default")
      (node (ref "JP1") (pin "37") (pinfunction "37_37") (pintype "passive"))
      (node (ref "MCU") (pin "70") (pinfunction "PB11/I2C2_SDA/USART3_RX/OTG_HS_ULPI_D4/ETH_RMII_TX_EN/ETH_MII_TX_EN/OTG_HS_SDA/TIM2_CH_70") (pintype "bidirectional"))
      (node (ref "P2") (pin "16") (pinfunction "16_16") (pintype "passive"))
    )
    (net (code "56") (name "/PB12") (class "Default")
      (node (ref "IC1") (pin "7") (pinfunction "SCLK_7") (pintype "passive"))
      (node (ref "MCU") (pin "73") (pinfunction "PB12/SPI2_NSS/I2S2_WS/I2C2_SMBA/USART3_CK/TIM1_BKIN/CAN2_RX/OTG_HS_ULPI_D5/ETH_RMII_TXD0/ETH_MII_TXD0/OTG_HS_ID_73") (pintype "bidirectional"))
    )
    (net (code "57") (name "/PB13") (class "Default")
      (node (ref "IC1") (pin "6") (pinfunction "I/O_6") (pintype "passive"))
      (node (ref "MCU") (pin "74") (pinfunction "PB13/SPI2_SCK/I2S2_SCK/USART3_CTS/TIM1_CH1N/CAN2_TX/OTG_HS_ULPI_D6/ETH_RMII_TXD1/ETH_MII_TXD1<>OTG_HS___VBUS_74") (pintype "bidirectional"))
    )
    (net (code "58") (name "/PB14") (class "Default")
      (node (ref "IC1") (pin "5") (pinfunction "CE_5") (pintype "passive"))
      (node (ref "MCU") (pin "75") (pinfunction "PB14/SPI2_MISO/TIM1_CH2N/TIM12_CH1/OTG_HS_DM/USART3_RTS/TIM8_CH2N_75") (pintype "bidirectional"))
    )
    (net (code "59") (name "/PC1") (class "Default")
      (node (ref "A9G") (pin "3") (pinfunction "3_3") (pintype "passive"))
      (node (ref "MCU") (pin "27") (pinfunction "PC1/ETH_MDC<>ADC123___IN11_27") (pintype "bidirectional"))
    )
    (net (code "60") (name "/PC4") (class "Default")
      (node (ref "MCU") (pin "44") (pinfunction "PC4/ETH_RMII_RX_D0/ETH_MII_RX_D0<>ADC12_IN14_44") (pintype "bidirectional"))
      (node (ref "RFID") (pin "7") (pinfunction "RST_7") (pintype "passive"))
    )
    (net (code "61") (name "/PC8") (class "Default")
      (node (ref "MCU") (pin "98") (pinfunction "PC8/TIM8_CH3/SDIO_D0/TIM3_CH3/USART6_CK/DCMI_D2_98") (pintype "bidirectional"))
      (node (ref "R5") (pin "1") (pintype "passive"))
      (node (ref "sdcard1") (pin "7") (pinfunction "DAT0_7") (pintype "passive"))
    )
    (net (code "62") (name "/PC13") (class "Default")
      (node (ref "JP1") (pin "33") (pinfunction "33_33") (pintype "passive"))
      (node (ref "MCU") (pin "7") (pinfunction "PC13<>RTC_AF1__7__7_7") (pintype "bidirectional"))
    )
    (net (code "63") (name "/PD2") (class "Default")
      (node (ref "MCU") (pin "116") (pinfunction "PD2/TIM3_ETR/UART5_RX/SDIO_CMD/DCMI_D11_116") (pintype "bidirectional"))
      (node (ref "R3") (pin "1") (pintype "passive"))
      (node (ref "sdcard1") (pin "3") (pinfunction "CMD_3") (pintype "passive"))
    )
    (net (code "64") (name "/PD3") (class "Default")
      (node (ref "MCU") (pin "117") (pinfunction "PD3/FSMC_CLK/USART2_CTS_117") (pintype "bidirectional"))
      (node (ref "sdcard1") (pin "9") (pinfunction "CK-IN_9") (pintype "passive"))
    )
    (net (code "65") (name "/PF11") (class "Default")
      (node (ref "JP1") (pin "30") (pinfunction "30_30") (pintype "passive"))
      (node (ref "MCU") (pin "49") (pinfunction "PF11/DCMI_12_49") (pintype "bidirectional"))
    )
    (net (code "66") (name "/PG9") (class "Default")
      (node (ref "A9G") (pin "4") (pinfunction "4_4") (pintype "passive"))
      (node (ref "MCU") (pin "124") (pinfunction "PG9/USART6_RX/FSMC_NE2/FSMC_NCE3_124") (pintype "bidirectional"))
      (node (ref "P3") (pin "1") (pinfunction "1_1") (pintype "passive"))
    )
    (net (code "67") (name "/PG14") (class "Default")
      (node (ref "A9G") (pin "5") (pinfunction "5_5") (pintype "passive"))
      (node (ref "MCU") (pin "129") (pinfunction "PG14/FSMC_A25/USART6_TX/ETH_MII_TXD1/ETH_RMII_TXD1_129") (pintype "bidirectional"))
      (node (ref "P3") (pin "2") (pinfunction "2_2") (pintype "passive"))
    )
    (net (code "68") (name "/RESET") (class "Default")
      (node (ref "C27") (pin "2") (pintype "passive"))
      (node (ref "JP1") (pin "5") (pinfunction "5_5") (pintype "passive"))
      (node (ref "MCU") (pin "25") (pinfunction "NRST_25") (pintype "input"))
      (node (ref "R16") (pin "1") (pintype "passive"))
      (node (ref "RST") (pin "1") (pinfunction "1_1") (pintype "passive"))
    )
    (net (code "69") (name "/SDIO_D1") (class "Default")
      (node (ref "MCU") (pin "99") (pinfunction "PC9/I2S2_CKIN/I2S3_CKIN/MCO2/TIM8_CH4/SDIO_D1/I2C3_SDA/DCMI_D3/TIM3_CH4_99") (pintype "bidirectional"))
      (node (ref "R6") (pin "1") (pintype "passive"))
      (node (ref "sdcard1") (pin "8") (pinfunction "DAT1_8") (pintype "passive"))
    )
    (net (code "70") (name "/SDIO_D2") (class "Default")
      (node (ref "MCU") (pin "111") (pinfunction "PC10/SPI3_SCK/I2S3_SCK/UART4_TX/SDIO_D2/DCMI_D8/USART3_TX_111") (pintype "bidirectional"))
      (node (ref "R1") (pin "1") (pintype "passive"))
      (node (ref "sdcard1") (pin "1") (pinfunction "DAT2_1") (pintype "passive"))
    )
    (net (code "71") (name "/SDIO_D3") (class "Default")
      (node (ref "R2") (pin "1") (pintype "passive"))
      (node (ref "sdcard1") (pin "2") (pinfunction "CD/DAT3_2") (pintype "passive"))
    )
    (net (code "72") (name "/SDIO_SCK") (class "Default")
      (node (ref "MCU") (pin "113") (pinfunction "PC12/UART5_TX/SDIO_CK/DCMI_D9/SPI3_MOSI/I2S3_SD/USART3_CK_113") (pintype "bidirectional"))
      (node (ref "R4") (pin "1") (pintype "passive"))
      (node (ref "sdcard1") (pin "5") (pinfunction "CLK_5") (pintype "passive"))
    )
    (net (code "73") (name "/VBAT") (class "Default")
      (node (ref "D3") (pin "2") (pinfunction "K_2") (pintype "passive"))
      (node (ref "IC1") (pin "8") (pinfunction "VCC1_8") (pintype "passive"))
      (node (ref "MCU") (pin "6") (pinfunction "VBAT_6") (pintype "power_in"))
    )
    (net (code "74") (name "/VCC4.0") (class "Default")
      (node (ref "P2") (pin "10") (pinfunction "10_10") (pintype "passive"))
      (node (ref "P2") (pin "9") (pinfunction "9_9") (pintype "passive"))
    )
    (net (code "75") (name "GND") (class "Default")
      (node (ref "A9G") (pin "2") (pinfunction "2_2") (pintype "passive"))
      (node (ref "BAT1") (pin "2") (pinfunction "GND_2") (pintype "passive"))
      (node (ref "C1") (pin "1") (pintype "passive"))
      (node (ref "C10") (pin "1") (pintype "passive"))
      (node (ref "C11") (pin "2") (pintype "passive"))
      (node (ref "C12") (pin "1") (pintype "passive"))
      (node (ref "C13") (pin "2") (pintype "passive"))
      (node (ref "C14") (pin "2") (pintype "passive"))
      (node (ref "C15") (pin "2") (pinfunction "2_2") (pintype "passive"))
      (node (ref "C16") (pin "1") (pinfunction "1_1") (pintype "passive"))
      (node (ref "C17") (pin "1") (pinfunction "1_1") (pintype "passive"))
      (node (ref "C18") (pin "1") (pinfunction "1_1") (pintype "passive"))
      (node (ref "C19") (pin "1") (pinfunction "1_1") (pintype "passive"))
      (node (ref "C2") (pin "2") (pinfunction "GND_2") (pintype "passive"))
      (node (ref "C20") (pin "1") (pinfunction "1_1") (pintype "passive"))
      (node (ref "C21") (pin "1") (pinfunction "1_1") (pintype "passive"))
      (node (ref "C22") (pin "1") (pinfunction "1_1") (pintype "passive"))
      (node (ref "C23") (pin "1") (pinfunction "1_1") (pintype "passive"))
      (node (ref "C24") (pin "2") (pinfunction "2_2") (pintype "passive"))
      (node (ref "C25") (pin "1") (pintype "passive"))
      (node (ref "C26") (pin "1") (pintype "passive"))
      (node (ref "C27") (pin "1") (pintype "passive"))
      (node (ref "C3") (pin "1") (pintype "passive"))
      (node (ref "C4") (pin "2") (pinfunction "GND_2") (pintype "passive"))
      (node (ref "C5") (pin "1") (pintype "passive"))
      (node (ref "C6") (pin "1") (pintype "passive"))
      (node (ref "C7") (pin "2") (pintype "passive"))
      (node (ref "C8") (pin "2") (pintype "passive"))
      (node (ref "C9") (pin "1") (pintype "passive"))
      (node (ref "CON1") (pin "2") (pintype "power_in"))
      (node (ref "CON1") (pin "3") (pintype "power_in"))
      (node (ref "D1") (pin "1") (pinfunction "A_1") (pintype "passive"))
      (node (ref "DOOR") (pin "2") (pinfunction "2_2") (pintype "passive"))
      (node (ref "DOOR") (pin "3") (pinfunction "3_3") (pintype "passive"))
      (node (ref "FINGER") (pin "5") (pinfunction "GND_5") (pintype "passive"))
      (node (ref "IC1") (pin "4") (pinfunction "GND_4") (pintype "passive"))
      (node (ref "JP1") (pin "22") (pinfunction "22_22") (pintype "passive"))
      (node (ref "JP1") (pin "26") (pinfunction "26_26") (pintype "passive"))
      (node (ref "JP1") (pin "27") (pinfunction "27_27") (pintype "passive"))
      (node (ref "K1") (pin "1") (pinfunction "1_1") (pintype "passive"))
      (node (ref "K2") (pin "1") (pinfunction "1_1") (pintype "passive"))
      (node (ref "LANYA") (pin "2") (pinfunction "GND_2") (pintype "passive"))
      (node (ref "MCU") (pin "107") (pinfunction "VSS_2_107") (pintype "power_in"))
      (node (ref "MCU") (pin "120") (pinfunction "VSS_10_120") (pintype "power_in"))
      (node (ref "MCU") (pin "130") (pinfunction "VSS_11_130") (pintype "power_in"))
      (node (ref "MCU") (pin "16") (pinfunction "VSS_5_16") (pintype "power_in"))
      (node (ref "MCU") (pin "31") (pinfunction "VSSA_31") (pintype "power_in"))
      (node (ref "MCU") (pin "32") (pinfunction "VREF+_32") (pintype "power_in"))
      (node (ref "MCU") (pin "38") (pinfunction "VSS_4_38") (pintype "power_in"))
      (node (ref "MCU") (pin "51") (pinfunction "VSS_6_51") (pintype "power_in"))
      (node (ref "MCU") (pin "61") (pinfunction "VSS_7_61") (pintype "power_in"))
      (node (ref "MCU") (pin "83") (pinfunction "VSS_8_83") (pintype "power_in"))
      (node (ref "MCU") (pin "94") (pinfunction "VSS_9_94") (pintype "power_in"))
      (node (ref "P2") (pin "5") (pinfunction "5_5") (pintype "passive"))
      (node (ref "P2") (pin "6") (pinfunction "6_6") (pintype "passive"))
      (node (ref "Q1") (pin "2") (pinfunction "E_2") (pintype "passive"))
      (node (ref "Q2") (pin "2") (pinfunction "E_2") (pintype "passive"))
      (node (ref "R7") (pin "1") (pintype "passive"))
      (node (ref "R9") (pin "1") (pinfunction "1_1") (pintype "passive"))
      (node (ref "RFID") (pin "6") (pinfunction "GND_6") (pintype "passive"))
      (node (ref "RST") (pin "2") (pinfunction "2_2") (pintype "passive"))
      (node (ref "SWD") (pin "1") (pinfunction "1_1") (pintype "passive"))
      (node (ref "U1") (pin "3") (pinfunction "GND_3") (pintype "passive"))
      (node (ref "U1") (pin "5") (pinfunction "ON/OFF_5") (pintype "passive"))
      (node (ref "U2") (pin "1") (pinfunction "GND_1") (pintype "passive"))
      (node (ref "sdcard1") (pin "6") (pinfunction "VSS_6") (pintype "passive"))
    )
    (net (code "76") (name "Net-(BAT1-VCC)") (class "Default")
      (node (ref "BAT1") (pin "1") (pinfunction "VCC_1") (pintype "passive"))
      (node (ref "D3") (pin "1") (pinfunction "A_1") (pintype "passive"))
    )
    (net (code "77") (name "Net-(BEEP1-G)") (class "Default")
      (node (ref "BEEP1") (pin "2") (pinfunction "G_2") (pintype "passive"))
      (node (ref "Q1") (pin "3") (pinfunction "C_3") (pintype "passive"))
    )
    (net (code "78") (name "Net-(CON1-Pad1)") (class "Default")
      (node (ref "CON1") (pin "1") (pintype "power_in"))
      (node (ref "FU1") (pin "1") (pinfunction "1_1") (pintype "passive"))
    )
    (net (code "79") (name "Net-(D1-K)") (class "Default")
      (node (ref "D1") (pin "2") (pinfunction "K_2") (pintype "passive"))
      (node (ref "L1") (pin "1") (pinfunction "1_1") (pintype "passive"))
      (node (ref "U1") (pin "2") (pinfunction "OUT_2") (pintype "passive"))
    )
    (net (code "80") (name "Net-(D2-A)") (class "Default")
      (node (ref "D2") (pin "1") (pinfunction "A_1") (pintype "passive"))
      (node (ref "FU1") (pin "2") (pinfunction "2_2") (pintype "passive"))
    )
    (net (code "81") (name "Net-(D2-K)") (class "Default")
      (node (ref "D2") (pin "2") (pinfunction "K_2") (pintype "passive"))
      (node (ref "S1") (pin "1") (pinfunction "I/O1_1") (pintype "passive"))
    )
    (net (code "82") (name "Net-(D4-A)") (class "Default")
      (node (ref "D4") (pin "1") (pinfunction "A_1") (pintype "passive"))
      (node (ref "JK1") (pin "2") (pinfunction "2_2") (pintype "passive"))
      (node (ref "Q2") (pin "3") (pinfunction "C_3") (pintype "passive"))
    )
    (net (code "83") (name "Net-(DOOR-Pad4)") (class "Default")
      (node (ref "DOOR") (pin "4") (pinfunction "4_4") (pintype "passive"))
      (node (ref "JK1") (pin "3") (pinfunction "3_3") (pintype "passive"))
    )
    (net (code "84") (name "Net-(DS1-A)") (class "Default")
      (node (ref "DS1") (pin "1") (pinfunction "A_1") (pintype "passive"))
      (node (ref "R17") (pin "2") (pintype "passive"))
    )
    (net (code "85") (name "Net-(DS2-A)") (class "Default")
      (node (ref "DS2") (pin "1") (pinfunction "A_1") (pintype "passive"))
      (node (ref "R18") (pin "2") (pintype "passive"))
    )
    (net (code "86") (name "Net-(DS3-A)") (class "Default")
      (node (ref "DS3") (pin "1") (pinfunction "A_1") (pintype "passive"))
      (node (ref "R19") (pin "2") (pintype "passive"))
    )
    (net (code "87") (name "Net-(IC1-X1)") (class "Default")
      (node (ref "C26") (pin "2") (pintype "passive"))
      (node (ref "IC1") (pin "2") (pinfunction "X1_2") (pintype "passive"))
      (node (ref "Y2") (pin "1") (pinfunction "OSC1_1") (pintype "passive"))
    )
    (net (code "88") (name "Net-(IC1-X2)") (class "Default")
      (node (ref "C25") (pin "2") (pintype "passive"))
      (node (ref "IC1") (pin "3") (pinfunction "X2_3") (pintype "passive"))
      (node (ref "Y2") (pin "2") (pinfunction "OSC2_2") (pintype "passive"))
    )
    (net (code "89") (name "Net-(LED1-K)") (class "Default")
      (node (ref "LED1") (pin "2") (pinfunction "K_2") (pintype "passive"))
      (node (ref "R7") (pin "2") (pintype "passive"))
    )
    (net (code "90") (name "Net-(MCU-PF8{slash}TIM13_CH1{slash}FSMC_NIOWR<>ADC3_IN6)") (class "Default")
      (node (ref "MCU") (pin "20") (pinfunction "PF8/TIM13_CH1/FSMC_NIOWR<>ADC3_IN6_20") (pintype "bidirectional"))
      (node (ref "R8") (pin "1") (pinfunction "1_1") (pintype "passive"))
    )
    (net (code "91") (name "Net-(MCU-VCAP_1)") (class "Default")
      (node (ref "C13") (pin "1") (pintype "passive"))
      (node (ref "MCU") (pin "71") (pinfunction "VCAP_1_71") (pintype "power_in"))
    )
    (net (code "92") (name "Net-(MCU-VCAP_2)") (class "Default")
      (node (ref "C14") (pin "1") (pintype "passive"))
      (node (ref "MCU") (pin "106") (pinfunction "VCAP_2_106") (pintype "power_in"))
    )
    (net (code "93") (name "Net-(P2-Pad3)") (class "Default")
      (node (ref "P2") (pin "3") (pinfunction "3_3") (pintype "passive"))
      (node (ref "R10") (pin "2") (pintype "passive"))
    )
    (net (code "94") (name "Net-(P2-Pad4)") (class "Default")
      (node (ref "P2") (pin "4") (pinfunction "4_4") (pintype "passive"))
      (node (ref "R11") (pin "1") (pintype "passive"))
    )
    (net (code "95") (name "Net-(Q1-B)") (class "Default")
      (node (ref "Q1") (pin "1") (pinfunction "B_1") (pintype "passive"))
      (node (ref "R8") (pin "2") (pinfunction "2_2") (pintype "passive"))
      (node (ref "R9") (pin "2") (pinfunction "2_2") (pintype "passive"))
    )
    (net (code "96") (name "Net-(Q2-B)") (class "Default")
      (node (ref "Q2") (pin "1") (pinfunction "B_1") (pintype "passive"))
      (node (ref "R15") (pin "2") (pintype "passive"))
    )
    (net (code "97") (name "VCC3.3") (class "Default")
      (node (ref "BEEP1") (pin "1") (pinfunction "P_1") (pintype "passive"))
      (node (ref "C1") (pin "2") (pintype "passive"))
      (node (ref "C10") (pin "2") (pintype "passive"))
      (node (ref "C11") (pin "1") (pintype "passive"))
      (node (ref "C16") (pin "2") (pinfunction "2_2") (pintype "passive"))
      (node (ref "C17") (pin "2") (pinfunction "2_2") (pintype "passive"))
      (node (ref "C18") (pin "2") (pinfunction "2_2") (pintype "passive"))
      (node (ref "C19") (pin "2") (pinfunction "2_2") (pintype "passive"))
      (node (ref "C20") (pin "2") (pinfunction "2_2") (pintype "passive"))
      (node (ref "C21") (pin "2") (pinfunction "2_2") (pintype "passive"))
      (node (ref "C22") (pin "2") (pinfunction "2_2") (pintype "passive"))
      (node (ref "C23") (pin "2") (pinfunction "2_2") (pintype "passive"))
      (node (ref "C9") (pin "2") (pintype "passive"))
      (node (ref "IC1") (pin "1") (pinfunction "VCC2_1") (pintype "passive"))
      (node (ref "JP1") (pin "24") (pinfunction "24_24") (pintype "passive"))
      (node (ref "JP1") (pin "25") (pinfunction "25_25") (pintype "passive"))
      (node (ref "LANYA") (pin "1") (pinfunction "VCC_1") (pintype "passive"))
      (node (ref "MCU") (pin "108") (pinfunction "VDD_2_108") (pintype "power_in"))
      (node (ref "MCU") (pin "121") (pinfunction "VDD_10_121") (pintype "power_in"))
      (node (ref "MCU") (pin "131") (pinfunction "VDD_11_131") (pintype "power_in"))
      (node (ref "MCU") (pin "144") (pinfunction "VDD_3_144") (pintype "power_in"))
      (node (ref "MCU") (pin "17") (pinfunction "VDD_5_17") (pintype "power_in"))
      (node (ref "MCU") (pin "30") (pinfunction "VDD_12_30") (pintype "power_in"))
      (node (ref "MCU") (pin "33") (pinfunction "VDDA_33") (pintype "power_in"))
      (node (ref "MCU") (pin "39") (pinfunction "VDD_4_39") (pintype "power_in"))
      (node (ref "MCU") (pin "52") (pinfunction "VDD_6_52") (pintype "power_in"))
      (node (ref "MCU") (pin "62") (pinfunction "VDD_7_62") (pintype "power_in"))
      (node (ref "MCU") (pin "72") (pinfunction "VDD_1_72") (pintype "power_in"))
      (node (ref "MCU") (pin "84") (pinfunction "VDD_8_84") (pintype "power_in"))
      (node (ref "MCU") (pin "95") (pinfunction "VDD_9_95") (pintype "power_in"))
      (node (ref "P2") (pin "1") (pinfunction "1_1") (pintype "passive"))
      (node (ref "P2") (pin "2") (pinfunction "2_2") (pintype "passive"))
      (node (ref "R1") (pin "2") (pintype "passive"))
      (node (ref "R13") (pin "2") (pintype "passive"))
      (node (ref "R14") (pin "2") (pintype "passive"))
      (node (ref "R16") (pin "2") (pintype "passive"))
      (node (ref "R17") (pin "1") (pintype "passive"))
      (node (ref "R18") (pin "1") (pintype "passive"))
      (node (ref "R19") (pin "1") (pintype "passive"))
      (node (ref "R2") (pin "2") (pintype "passive"))
      (node (ref "R3") (pin "2") (pintype "passive"))
      (node (ref "R4") (pin "2") (pintype "passive"))
      (node (ref "R5") (pin "2") (pintype "passive"))
      (node (ref "R6") (pin "2") (pintype "passive"))
      (node (ref "RFID") (pin "8") (pinfunction "3.3V_8") (pintype "passive"))
      (node (ref "U2") (pin "2") (pinfunction "OUT_2") (pintype "passive"))
      (node (ref "sdcard1") (pin "4") (pinfunction "VDD_4") (pintype "passive"))
    )
    (net (code "98") (name "VCC5") (class "Default")
      (node (ref "A9G") (pin "1") (pinfunction "1_1") (pintype "passive"))
      (node (ref "C12") (pin "2") (pintype "passive"))
      (node (ref "C4") (pin "1") (pinfunction "VCC_1") (pintype "passive"))
      (node (ref "C5") (pin "2") (pintype "passive"))
      (node (ref "C6") (pin "2") (pintype "passive"))
      (node (ref "C7") (pin "1") (pintype "passive"))
      (node (ref "C8") (pin "1") (pintype "passive"))
      (node (ref "FINGER") (pin "6") (pinfunction "VCC_6") (pintype "passive"))
      (node (ref "JP1") (pin "28") (pinfunction "28_28") (pintype "passive"))
      (node (ref "L1") (pin "2") (pinfunction "2_2") (pintype "passive"))
      (node (ref "LED1") (pin "1") (pinfunction "A_1") (pintype "passive"))
      (node (ref "P2") (pin "7") (pinfunction "7_7") (pintype "passive"))
      (node (ref "P2") (pin "8") (pinfunction "8_8") (pintype "passive"))
      (node (ref "U1") (pin "4") (pinfunction "FB_4") (pintype "passive"))
      (node (ref "U2") (pin "3") (pinfunction "IN_3") (pintype "passive"))
    )
    (net (code "99") (name "VCC12") (class "Default")
      (node (ref "C2") (pin "1") (pinfunction "VCC_1") (pintype "passive"))
      (node (ref "C3") (pin "2") (pintype "passive"))
      (node (ref "D4") (pin "2") (pinfunction "K_2") (pintype "passive"))
      (node (ref "DOOR") (pin "1") (pinfunction "1_1") (pintype "passive"))
      (node (ref "JK1") (pin "1") (pinfunction "1_1") (pintype "passive"))
      (node (ref "JK1") (pin "4") (pinfunction "4_4") (pintype "passive"))
      (node (ref "S1") (pin "2") (pinfunction "TAP1_2") (pintype "passive"))
      (node (ref "U1") (pin "1") (pinfunction "VIN_1") (pintype "passive"))
    )
    (net (code "100") (name "unconnected-(FINGER-BL-Pad2)") (class "Default")
      (node (ref "FINGER") (pin "2") (pinfunction "BL_2") (pintype "passive"))
    )
    (net (code "101") (name "unconnected-(FINGER-RST-Pad1)") (class "Default")
      (node (ref "FINGER") (pin "1") (pinfunction "RST_1") (pintype "passive"))
    )
    (net (code "102") (name "unconnected-(LANYA-KEY-Pad5)") (class "Default")
      (node (ref "LANYA") (pin "5") (pinfunction "KEY_5") (pintype "passive+no_connect"))
    )
    (net (code "103") (name "unconnected-(LANYA-LED-Pad6)") (class "Default")
      (node (ref "LANYA") (pin "6") (pinfunction "LED_6") (pintype "passive+no_connect"))
    )
    (net (code "104") (name "unconnected-(MCU-NC{slash}PDR_ON-Pad143)") (class "Default")
      (node (ref "MCU") (pin "143") (pinfunction "NC/PDR_ON_143") (pintype "power_in"))
    )
    (net (code "105") (name "unconnected-(MCU-PA11{slash}USART1_CTS{slash}CAN1_RX{slash}TIM1_CH4{slash}OTG_FS_DM-Pad103)") (class "Default")
      (node (ref "MCU") (pin "103") (pinfunction "PA11/USART1_CTS/CAN1_RX/TIM1_CH4/OTG_FS_DM_103") (pintype "bidirectional"))
    )
    (net (code "106") (name "unconnected-(MCU-PA12{slash}USART1_RTS{slash}CAN1_TX{slash}TIM1_ETR{slash}OTG_FS_DP-Pad104)") (class "Default")
      (node (ref "MCU") (pin "104") (pinfunction "PA12/USART1_RTS/CAN1_TX/TIM1_ETR/OTG_FS_DP_104") (pintype "bidirectional"))
    )
    (net (code "107") (name "unconnected-(MCU-PB7{slash}I2C1_SDA{slash}FSMC_NL{slash}DCMI_VSYNC{slash}USART1_RX{slash}TIM4_CH2-Pad137)") (class "Default")
      (node (ref "MCU") (pin "137") (pinfunction "PB7/I2C1_SDA/FSMC_NL/DCMI_VSYNC/USART1_RX/TIM4_CH2_137") (pintype "bidirectional"))
    )
    (net (code "108") (name "unconnected-(MCU-PB8{slash}TIM4_CH3{slash}SDIO_D4{slash}TIM10_CH1{slash}DCMI_D6{slash}OTG_FS_SCL{slash}ETH_MII_TXD3{slash}I2C1_SCL{slash}CAN1_RX-Pad139)") (class "Default")
      (node (ref "MCU") (pin "139") (pinfunction "PB8/TIM4_CH3/SDIO_D4/TIM10_CH1/DCMI_D6/OTG_FS_SCL/ETH_MII_TXD3/I2C1_SCL/CAN1_RX_139") (pintype "bidirectional"))
    )
    (net (code "109") (name "unconnected-(MCU-PB9{slash}SPI2_NSS{slash}I2S2_WS{slash}TIM4_CH4{slash}TIM11_CH1{slash}OTG_FS_SDA{slash}SDIO_D5{slash}DCMI_D7{slash}I2C1_SDA{slash}CAN1_TX-Pad140)") (class "Default")
      (node (ref "MCU") (pin "140") (pinfunction "PB9/SPI2_NSS/I2S2_WS/TIM4_CH4/TIM11_CH1/OTG_FS_SDA/SDIO_D5/DCMI_D7/I2C1_SDA/CAN1_TX_140") (pintype "bidirectional"))
    )
    (net (code "110") (name "unconnected-(MCU-PC0{slash}OTG_HS_ULPI_STP<>ADC123___IN10-Pad26)") (class "Default")
      (node (ref "MCU") (pin "26") (pinfunction "PC0/OTG_HS_ULPI_STP<>ADC123___IN10_26") (pintype "bidirectional"))
    )
    (net (code "111") (name "unconnected-(MCU-PC2{slash}SPI2_MISO{slash}OTG_HS_ULPI_DIR{slash}ETH_MII_TXD2<>ADC123___IN12-Pad28)") (class "Default")
      (node (ref "MCU") (pin "28") (pinfunction "PC2/SPI2_MISO/OTG_HS_ULPI_DIR/ETH_MII_TXD2<>ADC123___IN12_28") (pintype "bidirectional"))
    )
    (net (code "112") (name "unconnected-(MCU-PC3{slash}SPI2_MOSI{slash}I2S2_SD{slash}OTG_HS_ULPI_NXT{slash}ETH_MII_TX_CLK<>ADC123___IN13-Pad29)") (class "Default")
      (node (ref "MCU") (pin "29") (pinfunction "PC3/SPI2_MOSI/I2S2_SD/OTG_HS_ULPI_NXT/ETH_MII_TX_CLK<>ADC123___IN13_29") (pintype "bidirectional"))
    )
    (net (code "113") (name "unconnected-(MCU-PC5{slash}ETH_RMII_RX_D1{slash}ETH_MII_RX_D1<>ADC12_IN15-Pad45)") (class "Default")
      (node (ref "MCU") (pin "45") (pinfunction "PC5/ETH_RMII_RX_D1/ETH_MII_RX_D1<>ADC12_IN15_45") (pintype "bidirectional"))
    )
    (net (code "114") (name "unconnected-(MCU-PC6{slash}SPI2_MCK{slash}TIM8_CH1{slash}SDIO_D6{slash}USART6_TX{slash}DCMI_D0{slash}TIM3_CH1-Pad96)") (class "Default")
      (node (ref "MCU") (pin "96") (pinfunction "PC6/SPI2_MCK/TIM8_CH1/SDIO_D6/USART6_TX/DCMI_D0/TIM3_CH1_96") (pintype "bidirectional"))
    )
    (net (code "115") (name "unconnected-(MCU-PC7{slash}SPI3_MCK{slash}TIM8_CH2{slash}SDIO_D7{slash}USART6_RX{slash}DCMI_D1{slash}TIM3_CH2-Pad97)") (class "Default")
      (node (ref "MCU") (pin "97") (pinfunction "PC7/SPI3_MCK/TIM8_CH2/SDIO_D7/USART6_RX/DCMI_D1/TIM3_CH2_97") (pintype "bidirectional"))
    )
    (net (code "116") (name "unconnected-(MCU-PC11{slash}UART4_RX{slash}_SPI3_MISO{slash}SDIO_D3{slash}DCMI_D4{slash}USART3_RX-Pad112)") (class "Default")
      (node (ref "MCU") (pin "112") (pinfunction "PC11/UART4_RX/_SPI3_MISO/SDIO_D3/DCMI_D4/USART3_RX_112") (pintype "bidirectional"))
    )
    (net (code "117") (name "unconnected-(MCU-PC14<>OSC32_IN-Pad8)") (class "Default")
      (node (ref "MCU") (pin "8") (pinfunction "PC14<>OSC32_IN_8") (pintype "bidirectional"))
    )
    (net (code "118") (name "unconnected-(MCU-PC15<>OSC32_OUT-Pad9)") (class "Default")
      (node (ref "MCU") (pin "9") (pinfunction "PC15<>OSC32_OUT_9") (pintype "bidirectional"))
    )
    (net (code "119") (name "unconnected-(MCU-PD6{slash}FSMC_NWAIT{slash}USART2_RX-Pad122)") (class "Default")
      (node (ref "MCU") (pin "122") (pinfunction "PD6/FSMC_NWAIT/USART2_RX_122") (pintype "bidirectional"))
    )
    (net (code "120") (name "unconnected-(MCU-PD7{slash}USART2_CK{slash}FSMC_NE1{slash}FSMC_NCE2-Pad123)") (class "Default")
      (node (ref "MCU") (pin "123") (pinfunction "PD7/USART2_CK/FSMC_NE1/FSMC_NCE2_123") (pintype "bidirectional"))
    )
    (net (code "121") (name "unconnected-(MCU-PD11{slash}FSMC_A16{slash}USART3_CTS-Pad80)") (class "Default")
      (node (ref "MCU") (pin "80") (pinfunction "PD11/FSMC_A16/USART3_CTS_80") (pintype "bidirectional"))
    )
    (net (code "122") (name "unconnected-(MCU-PD12{slash}FSMC_A17{slash}TIM4_CH1{slash}USART3_RTS-Pad81)") (class "Default")
      (node (ref "MCU") (pin "81") (pinfunction "PD12/FSMC_A17/TIM4_CH1/USART3_RTS_81") (pintype "bidirectional"))
    )
    (net (code "123") (name "unconnected-(MCU-PD13{slash}FSMC_A18{slash}TIM4_CH2-Pad82)") (class "Default")
      (node (ref "MCU") (pin "82") (pinfunction "PD13/FSMC_A18/TIM4_CH2_82") (pintype "bidirectional"))
    )
    (net (code "124") (name "unconnected-(MCU-PE0{slash}TIM4_ETR{slash}FSMC_NBL0{slash}DCMI_D2-Pad141)") (class "Default")
      (node (ref "MCU") (pin "141") (pinfunction "PE0/TIM4_ETR/FSMC_NBL0/DCMI_D2_141") (pintype "bidirectional"))
    )
    (net (code "125") (name "unconnected-(MCU-PE1{slash}FSMC_NBL1{slash}DCMI_D3-Pad142)") (class "Default")
      (node (ref "MCU") (pin "142") (pinfunction "PE1/FSMC_NBL1/DCMI_D3_142") (pintype "bidirectional"))
    )
    (net (code "126") (name "unconnected-(MCU-PF0{slash}FSMC_A0{slash}I2C2_SDA-Pad10)") (class "Default")
      (node (ref "MCU") (pin "10") (pinfunction "PF0/FSMC_A0/I2C2_SDA_10") (pintype "bidirectional"))
    )
    (net (code "127") (name "unconnected-(MCU-PF1{slash}FSMC_A1{slash}I2C2_SC-Pad11)") (class "Default")
      (node (ref "MCU") (pin "11") (pinfunction "PF1/FSMC_A1/I2C2_SC_11") (pintype "bidirectional"))
    )
    (net (code "128") (name "unconnected-(MCU-PF2{slash}FSMC_A2{slash}I2C2_SMBA-Pad12)") (class "Default")
      (node (ref "MCU") (pin "12") (pinfunction "PF2/FSMC_A2/I2C2_SMBA_12") (pintype "bidirectional"))
    )
    (net (code "129") (name "unconnected-(MCU-PF3{slash}FSMC_A3<>ADC3_IN9-Pad13)") (class "Default")
      (node (ref "MCU") (pin "13") (pinfunction "PF3/FSMC_A3<>ADC3_IN9_13") (pintype "bidirectional"))
    )
    (net (code "130") (name "unconnected-(MCU-PF4{slash}FSMC_A4<>ADC3_IN14-Pad14)") (class "Default")
      (node (ref "MCU") (pin "14") (pinfunction "PF4/FSMC_A4<>ADC3_IN14_14") (pintype "bidirectional"))
    )
    (net (code "131") (name "unconnected-(MCU-PF5{slash}FSMC_A5<>ADC3_IN15-Pad15)") (class "Default")
      (node (ref "MCU") (pin "15") (pinfunction "PF5/FSMC_A5<>ADC3_IN15_15") (pintype "bidirectional"))
    )
    (net (code "132") (name "unconnected-(MCU-PF6{slash}TIM10_CH1{slash}FSMC_NIORD<>ADC3_IN4-Pad18)") (class "Default")
      (node (ref "MCU") (pin "18") (pinfunction "PF6/TIM10_CH1/FSMC_NIORD<>ADC3_IN4_18") (pintype "bidirectional"))
    )
    (net (code "133") (name "unconnected-(MCU-PF7{slash}TIM11_CH1{slash}FSMC_NREG<>ADC3_IN5-Pad19)") (class "Default")
      (node (ref "MCU") (pin "19") (pinfunction "PF7/TIM11_CH1/FSMC_NREG<>ADC3_IN5_19") (pintype "bidirectional"))
    )
    (net (code "134") (name "unconnected-(MCU-PF9{slash}TIM14_CH1{slash}FSMC_CD<>ADC3_IN7-Pad21)") (class "Default")
      (node (ref "MCU") (pin "21") (pinfunction "PF9/TIM14_CH1/FSMC_CD<>ADC3_IN7_21") (pintype "bidirectional"))
    )
    (net (code "135") (name "unconnected-(MCU-PF10{slash}FSMC_INTR<>ADC3_IN8-Pad22)") (class "Default")
      (node (ref "MCU") (pin "22") (pinfunction "PF10/FSMC_INTR<>ADC3_IN8_22") (pintype "bidirectional"))
    )
    (net (code "136") (name "unconnected-(MCU-PF13{slash}FSMC_A7-Pad53)") (class "Default")
      (node (ref "MCU") (pin "53") (pinfunction "PF13/FSMC_A7_53") (pintype "bidirectional"))
    )
    (net (code "137") (name "unconnected-(MCU-PF14{slash}FSMC_A8-Pad54)") (class "Default")
      (node (ref "MCU") (pin "54") (pinfunction "PF14/FSMC_A8_54") (pintype "bidirectional"))
    )
    (net (code "138") (name "unconnected-(MCU-PF15{slash}FSMC_A9-Pad55)") (class "Default")
      (node (ref "MCU") (pin "55") (pinfunction "PF15/FSMC_A9_55") (pintype "bidirectional"))
    )
    (net (code "139") (name "unconnected-(MCU-PG0{slash}FSMC_A10-Pad56)") (class "Default")
      (node (ref "MCU") (pin "56") (pinfunction "PG0/FSMC_A10_56") (pintype "bidirectional"))
    )
    (net (code "140") (name "unconnected-(MCU-PG1{slash}FSMC_A11-Pad57)") (class "Default")
      (node (ref "MCU") (pin "57") (pinfunction "PG1/FSMC_A11_57") (pintype "bidirectional"))
    )
    (net (code "141") (name "unconnected-(MCU-PG2{slash}FSMC_A12-Pad87)") (class "Default")
      (node (ref "MCU") (pin "87") (pinfunction "PG2/FSMC_A12_87") (pintype "bidirectional"))
    )
    (net (code "142") (name "unconnected-(MCU-PG3{slash}FSMC_A13-Pad88)") (class "Default")
      (node (ref "MCU") (pin "88") (pinfunction "PG3/FSMC_A13_88") (pintype "bidirectional"))
    )
    (net (code "143") (name "unconnected-(MCU-PG4{slash}FSMC_A14-Pad89)") (class "Default")
      (node (ref "MCU") (pin "89") (pinfunction "PG4/FSMC_A14_89") (pintype "bidirectional"))
    )
    (net (code "144") (name "unconnected-(MCU-PG5{slash}FSMC_A15-Pad90)") (class "Default")
      (node (ref "MCU") (pin "90") (pinfunction "PG5/FSMC_A15_90") (pintype "bidirectional"))
    )
    (net (code "145") (name "unconnected-(MCU-PG6{slash}FSMC_INT2-Pad91)") (class "Default")
      (node (ref "MCU") (pin "91") (pinfunction "PG6/FSMC_INT2_91") (pintype "bidirectional"))
    )
    (net (code "146") (name "unconnected-(MCU-PG7{slash}FSMC_INT3{slash}USART6_CK-Pad92)") (class "Default")
      (node (ref "MCU") (pin "92") (pinfunction "PG7/FSMC_INT3/USART6_CK_92") (pintype "bidirectional"))
    )
    (net (code "147") (name "unconnected-(MCU-PG10{slash}FSMC_NCE4_1{slash}FSMC_NE3-Pad125)") (class "Default")
      (node (ref "MCU") (pin "125") (pinfunction "PG10/FSMC_NCE4_1/FSMC_NE3_125") (pintype "bidirectional"))
    )
    (net (code "148") (name "unconnected-(MCU-PG11{slash}FSMC_NCE4_2{slash}ETH_MII_TX_EN-Pad126)") (class "Default")
      (node (ref "MCU") (pin "126") (pinfunction "PG11/FSMC_NCE4_2/ETH_MII_TX_EN_126") (pintype "bidirectional"))
    )
    (net (code "149") (name "unconnected-(MCU-PG13{slash}FSMC_A24{slash}USART6_CTS{slash}ETH_MII_TXD0{slash}ETH_RMII___TXD0-Pad128)") (class "Default")
      (node (ref "MCU") (pin "128") (pinfunction "PG13/FSMC_A24/USART6_CTS/ETH_MII_TXD0/ETH_RMII___TXD0_128") (pintype "bidirectional"))
    )
    (net (code "150") (name "unconnected-(MCU-PG15{slash}USART6_CTS{slash}DCMI_D13-Pad132)") (class "Default")
      (node (ref "MCU") (pin "132") (pinfunction "PG15/USART6_CTS/DCMI_D13_132") (pintype "bidirectional"))
    )
    (net (code "151") (name "unconnected-(MCU-{slash}USART6_RTS{slash}ETH_PPS_OUT-Pad93)") (class "Default")
      (node (ref "MCU") (pin "93") (pinfunction "/USART6_RTS/ETH_PPS_OUT_93") (pintype "bidirectional"))
    )
    (net (code "152") (name "unconnected-(RFID-IRQ-Pad5)") (class "Default")
      (node (ref "RFID") (pin "5") (pinfunction "IRQ_5") (pintype "passive"))
    )
    (net (code "153") (name "unconnected-(S1-I{slash}O1-Pad3)") (class "Default")
      (node (ref "S1") (pin "3") (pinfunction "I/O1_3") (pintype "passive"))
    )
    (net (code "154") (name "unconnected-(S1-I{slash}O2-Pad4)") (class "Default")
      (node (ref "S1") (pin "4") (pinfunction "I/O2_4") (pintype "passive"))
    )
    (net (code "155") (name "unconnected-(S1-I{slash}O2-Pad6)") (class "Default")
      (node (ref "S1") (pin "6") (pinfunction "I/O2_6") (pintype "passive"))
    )
    (net (code "156") (name "unconnected-(S1-TAP2-Pad5)") (class "Default")
      (node (ref "S1") (pin "5") (pinfunction "TAP2_5") (pintype "passive"))
    )
    (net (code "157") (name "unconnected-(U2-OUT-Pad4)") (class "Default")
      (node (ref "U2") (pin "4") (pinfunction "OUT_4") (pintype "passive"))
    )
    (net (code "158") (name "unconnected-(sdcard1-CK-OUT-Pad10)") (class "Default")
      (node (ref "sdcard1") (pin "10") (pinfunction "CK-OUT_10") (pintype "passive"))
    )
  )
)
